# betaV2_3.net
KiCad netlist of a schematic drawn in Altium Designer
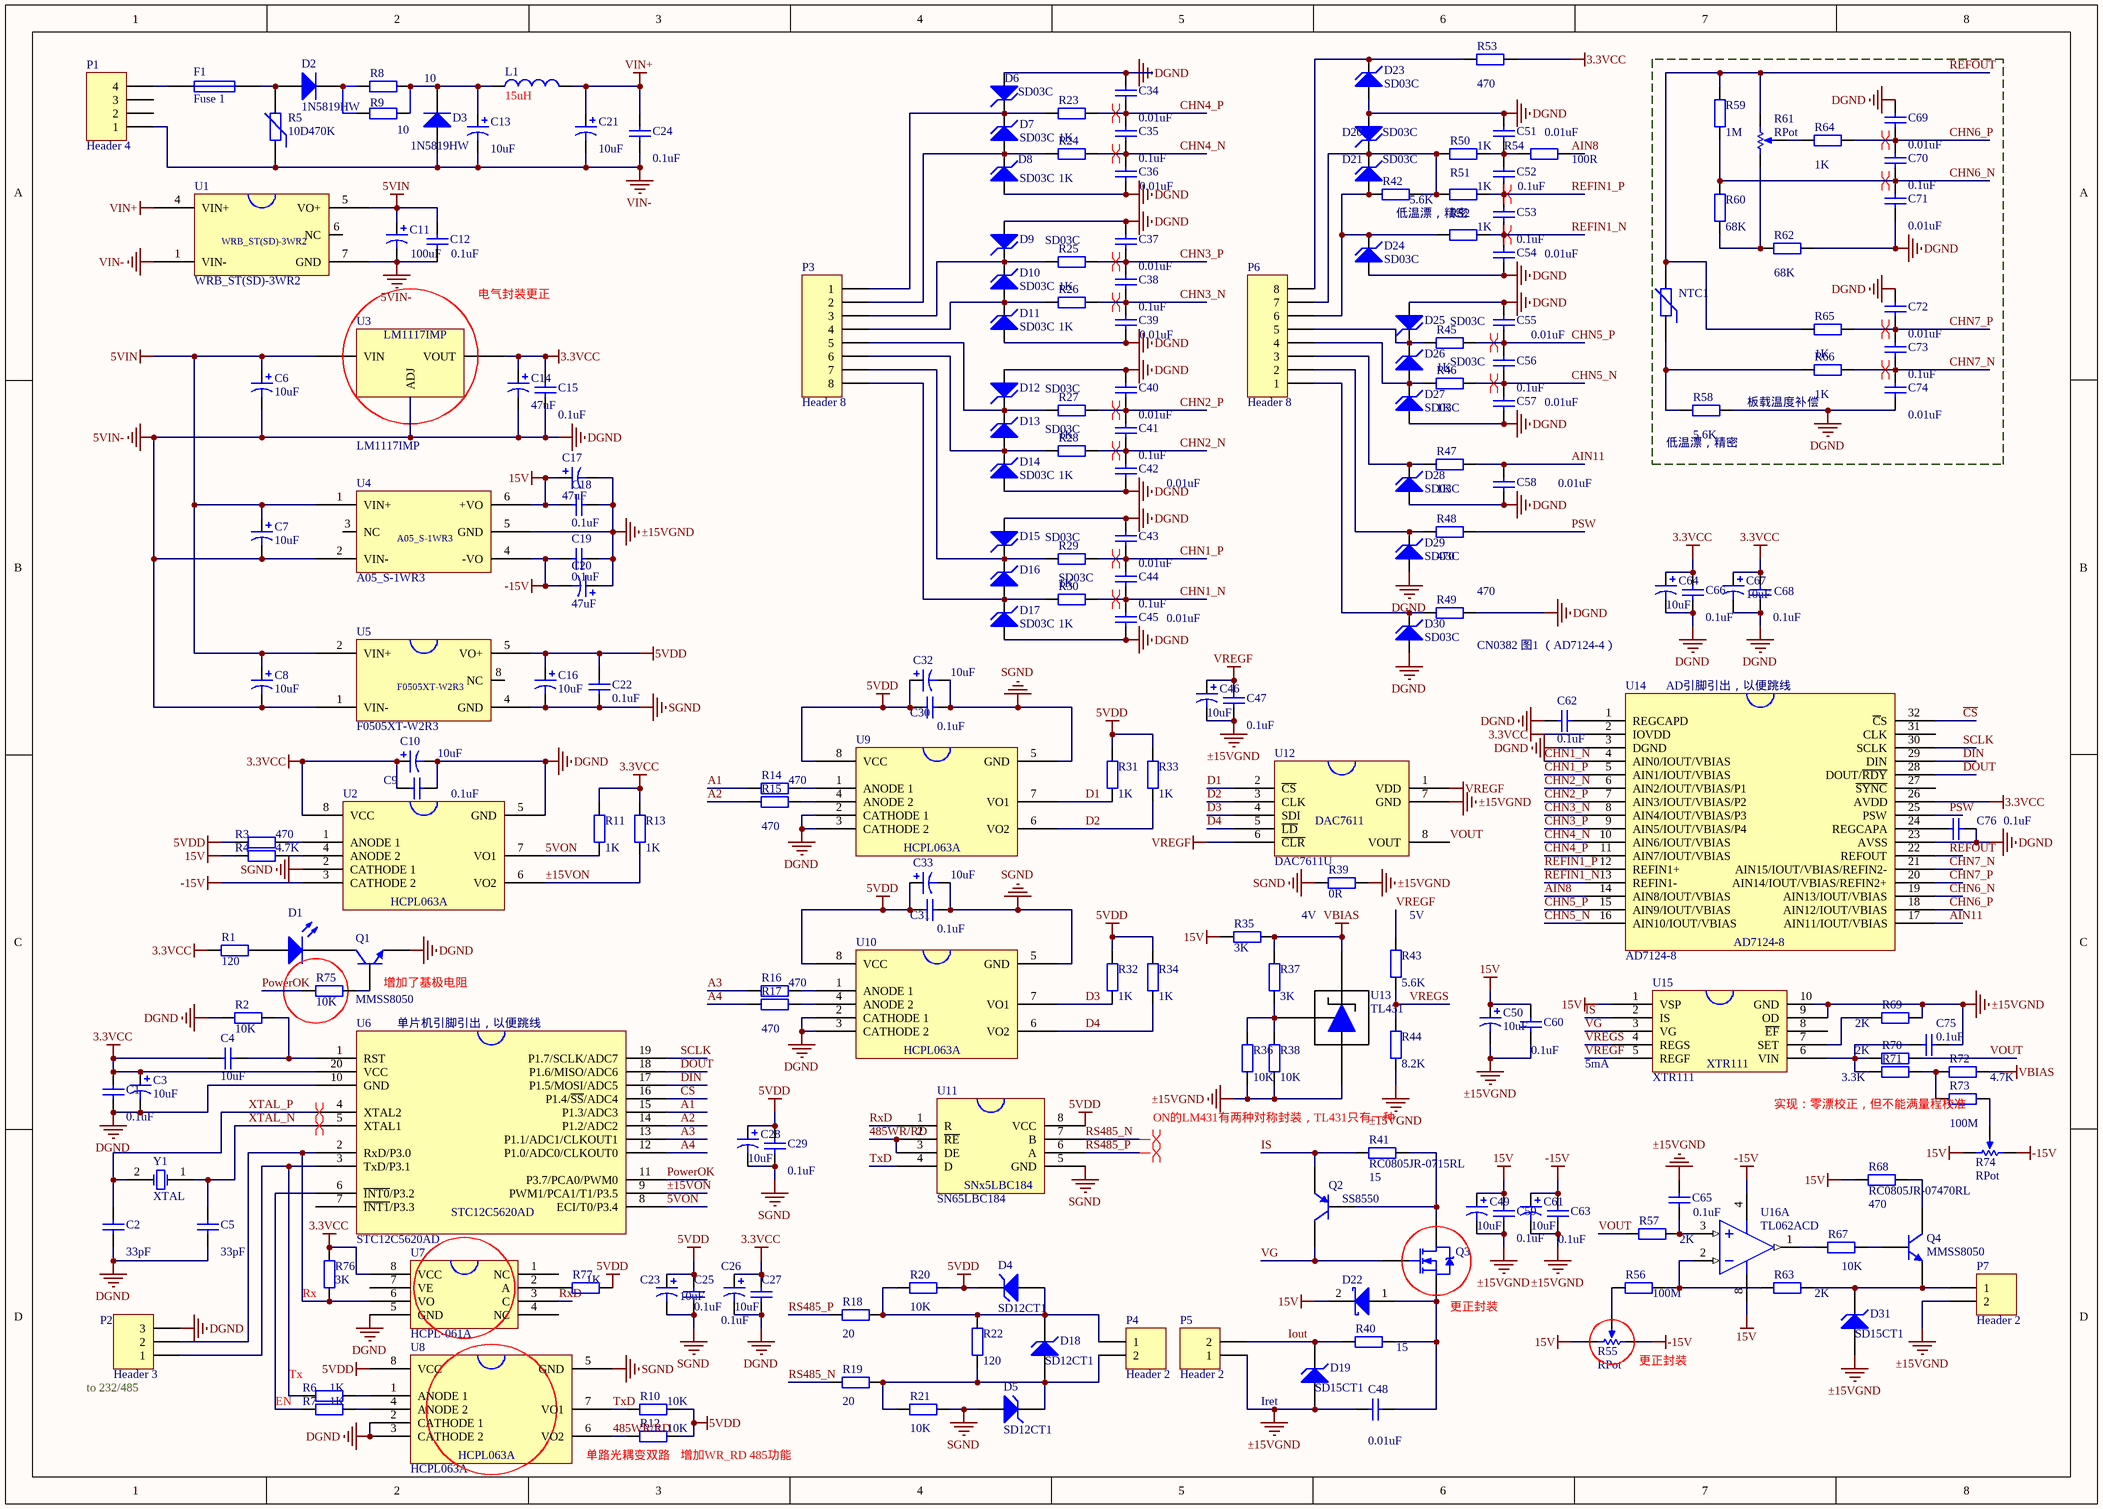
[diagram p0: betaV2.3.SchDoc]

(export (version "E")
  (design (tool "Eeschema 10.0.6"))
  (components
    (comp (ref "C1")
      (value "0.1uF")
      (footprint "0805c")
      (description "Capacitor")
      (fields (field (name "Comment") "CC0805MRX7R9BB104"))
      (libsource (lib "Miscellaneous Devices") (part "Cap"))
    )
    (comp (ref "C2")
      (value "33pF")
      (footprint "0805c")
      (description "Capacitor")
      (fields (field (name "Comment") "CC0805MRX7R9BB330") (field (name "PUBLISHER") "Altium Limited"))
      (libsource (lib "Miscellaneous Devices") (part "Cap"))
    )
    (comp (ref "C3")
      (value "10uF")
      (footprint "CB")
      (description "Polarized Capacitor (Radial)")
      (fields (field (name "Comment") "T494B106M006AHAUTO") (field (name "PUBLISHER") "Altium Limited"))
      (libsource (lib "Miscellaneous Devices") (part "Cap Pol1"))
    )
    (comp (ref "C4")
      (value "10uF")
      (footprint "0805c")
      (description "Capacitor")
      (fields (field (name "Comment") "CC0805MRX7R9BB106"))
      (libsource (lib "Miscellaneous Devices") (part "Cap"))
    )
    (comp (ref "C5")
      (value "33pF")
      (footprint "0805c")
      (description "Capacitor")
      (fields (field (name "Comment") "CC0805MRX7R9BB330") (field (name "PUBLISHER") "Altium Limited"))
      (libsource (lib "Miscellaneous Devices") (part "Cap"))
    )
    (comp (ref "C6")
      (value "10uF")
      (footprint "CB")
      (description "Polarized Capacitor (Radial)")
      (fields (field (name "Comment") "T494B106M006AHAUTO") (field (name "PUBLISHER") "Altium Limited"))
      (libsource (lib "Miscellaneous Devices") (part "Cap Pol1"))
    )
    (comp (ref "C7")
      (value "10uF")
      (footprint "CB")
      (description "Polarized Capacitor (Radial)")
      (fields (field (name "Comment") "T494B106M006AHAUTO") (field (name "PUBLISHER") "Altium Limited"))
      (libsource (lib "Miscellaneous Devices") (part "Cap Pol1"))
    )
    (comp (ref "C8")
      (value "10uF")
      (footprint "CB")
      (description "Polarized Capacitor (Radial)")
      (fields (field (name "Comment") "T494B106M006AHAUTO") (field (name "PUBLISHER") "Altium Limited"))
      (libsource (lib "Miscellaneous Devices") (part "Cap Pol1"))
    )
    (comp (ref "C9")
      (value "0.1uF")
      (footprint "0805c")
      (description "Capacitor")
      (fields (field (name "Comment") "CC0805MRX7R9BB104") (field (name "PUBLISHER") "Altium Limited"))
      (libsource (lib "Miscellaneous Devices") (part "Cap"))
    )
    (comp (ref "C10")
      (value "10uF")
      (footprint "CB")
      (description "Polarized Capacitor (Radial)")
      (fields (field (name "Comment") "T494B106M006AHAUTO") (field (name "PUBLISHER") "Altium Limited"))
      (libsource (lib "Miscellaneous Devices") (part "Cap Pol1"))
    )
    (comp (ref "C11")
      (value "100uF")
      (footprint "CB")
      (description "Polarized Capacitor (Radial)")
      (fields (field (name "Comment") "T494B107M006AHAUTO") (field (name "PUBLISHER") "Altium Limited"))
      (libsource (lib "Miscellaneous Devices") (part "Cap Pol1"))
    )
    (comp (ref "C12")
      (value "0.1uF")
      (footprint "0805c")
      (description "Capacitor")
      (fields (field (name "Comment") "CC0805MRX7R9BB104") (field (name "PUBLISHER") "Altium Limited"))
      (libsource (lib "Miscellaneous Devices") (part "Cap"))
    )
    (comp (ref "C13")
      (value "10uF")
      (footprint "Φ6.3×11.5")
      (description "Polarized Capacitor (Radial)")
      (fields (field (name "Comment") "ECR1HQG100M-063007") (field (name "PUBLISHER") "Altium Limited"))
      (libsource (lib "Miscellaneous Devices") (part "Cap Pol1"))
    )
    (comp (ref "C14")
      (value "47uF")
      (footprint "CB")
      (description "Polarized Capacitor (Radial)")
      (fields (field (name "Comment") "T494B476M010AHAUTO") (field (name "PUBLISHER") "Altium Limited"))
      (libsource (lib "Miscellaneous Devices") (part "Cap Pol1"))
    )
    (comp (ref "C15")
      (value "0.1uF")
      (footprint "0805c")
      (description "Capacitor")
      (fields (field (name "Comment") "CC0805MRX7R9BB104") (field (name "PUBLISHER") "Altium Limited"))
      (libsource (lib "Miscellaneous Devices") (part "Cap"))
    )
    (comp (ref "C16")
      (value "10uF")
      (footprint "CB")
      (description "Polarized Capacitor (Radial)")
      (fields (field (name "Comment") "T494B106M006AHAUTO") (field (name "PUBLISHER") "Altium Limited"))
      (libsource (lib "Miscellaneous Devices") (part "Cap Pol1"))
    )
    (comp (ref "C17")
      (value "47uF")
      (footprint "CB")
      (description "Polarized Capacitor (Radial)")
      (fields (field (name "Comment") "T494B476K025ATAUTO") (field (name "PUBLISHER") "Altium Limited"))
      (libsource (lib "Miscellaneous Devices") (part "Cap Pol1"))
    )
    (comp (ref "C18")
      (value "0.1uF")
      (footprint "0805c")
      (description "Capacitor")
      (fields (field (name "Comment") "CC0805MRX7R9BB104") (field (name "PUBLISHER") "Altium Limited"))
      (libsource (lib "Miscellaneous Devices") (part "Cap"))
    )
    (comp (ref "C19")
      (value "0.1uF")
      (footprint "0805c")
      (description "Capacitor")
      (fields (field (name "Comment") "CC0805MRX7R9BB104") (field (name "PUBLISHER") "Altium Limited"))
      (libsource (lib "Miscellaneous Devices") (part "Cap"))
    )
    (comp (ref "C20")
      (value "47uF")
      (footprint "CB")
      (description "Polarized Capacitor (Radial)")
      (fields (field (name "Comment") "T494B476K025ATAUTO") (field (name "PUBLISHER") "Altium Limited"))
      (libsource (lib "Miscellaneous Devices") (part "Cap Pol1"))
    )
    (comp (ref "C21")
      (value "10uF")
      (footprint "Φ6.3×11.5")
      (description "Polarized Capacitor (Radial)")
      (fields (field (name "Comment") "ECR1HQG100M-063007") (field (name "PUBLISHER") "Altium Limited"))
      (libsource (lib "Miscellaneous Devices") (part "Cap Pol1"))
    )
    (comp (ref "C22")
      (value "0.1uF")
      (footprint "0805c")
      (description "Capacitor")
      (fields (field (name "Comment") "CC0805MRX7R9BB104") (field (name "PUBLISHER") "Altium Limited"))
      (libsource (lib "Miscellaneous Devices") (part "Cap"))
    )
    (comp (ref "C23")
      (value "10uF")
      (footprint "CB")
      (description "Polarized Capacitor (Radial)")
      (fields (field (name "Comment") "T494B106M006AHAUTO") (field (name "PUBLISHER") "Altium Limited"))
      (libsource (lib "Miscellaneous Devices") (part "Cap Pol1"))
    )
    (comp (ref "C24")
      (value "0.1uF")
      (footprint "0805c")
      (description "Capacitor")
      (fields (field (name "Comment") "CC0805MRX7R9BB104") (field (name "PUBLISHER") "Altium Limited"))
      (libsource (lib "Miscellaneous Devices") (part "Cap"))
    )
    (comp (ref "C25")
      (value "0.1uF")
      (footprint "0805c")
      (description "Capacitor")
      (fields (field (name "Comment") "CC0805MRX7R9BB104") (field (name "PUBLISHER") "Altium Limited"))
      (libsource (lib "Miscellaneous Devices") (part "Cap"))
    )
    (comp (ref "C26")
      (value "10uF")
      (footprint "CB")
      (description "Polarized Capacitor (Radial)")
      (fields (field (name "Comment") "T494B106M006AHAUTO") (field (name "PUBLISHER") "Altium Limited"))
      (libsource (lib "Miscellaneous Devices") (part "Cap Pol1"))
    )
    (comp (ref "C27")
      (value "0.1uF")
      (footprint "0805c")
      (description "Capacitor")
      (fields (field (name "Comment") "CC0805MRX7R9BB104") (field (name "PUBLISHER") "Altium Limited"))
      (libsource (lib "Miscellaneous Devices") (part "Cap"))
    )
    (comp (ref "C28")
      (value "10uF")
      (footprint "CB")
      (description "Polarized Capacitor (Radial)")
      (fields (field (name "Comment") "T494B106M006AHAUTO") (field (name "PUBLISHER") "Altium Limited"))
      (libsource (lib "Miscellaneous Devices") (part "Cap Pol1"))
    )
    (comp (ref "C29")
      (value "0.1uF")
      (footprint "0805c")
      (description "Capacitor")
      (fields (field (name "Comment") "CC0805MRX7R9BB104") (field (name "PUBLISHER") "Altium Limited"))
      (libsource (lib "Miscellaneous Devices") (part "Cap"))
    )
    (comp (ref "C30")
      (value "0.1uF")
      (footprint "0805c")
      (description "Capacitor")
      (fields (field (name "Comment") "CC0805MRX7R9BB104") (field (name "PUBLISHER") "Altium Limited"))
      (libsource (lib "Miscellaneous Devices") (part "Cap"))
    )
    (comp (ref "C31")
      (value "0.1uF")
      (footprint "0805c")
      (description "Capacitor")
      (fields (field (name "Comment") "CC0805MRX7R9BB104") (field (name "PUBLISHER") "Altium Limited"))
      (libsource (lib "Miscellaneous Devices") (part "Cap"))
    )
    (comp (ref "C32")
      (value "10uF")
      (footprint "CB")
      (description "Polarized Capacitor (Radial)")
      (fields (field (name "Comment") "T494B106M006AHAUTO") (field (name "PUBLISHER") "Altium Limited"))
      (libsource (lib "Miscellaneous Devices") (part "Cap Pol1"))
    )
    (comp (ref "C33")
      (value "10uF")
      (footprint "CB")
      (description "Polarized Capacitor (Radial)")
      (fields (field (name "Comment") "T494B106M006AHAUTO") (field (name "PUBLISHER") "Altium Limited"))
      (libsource (lib "Miscellaneous Devices") (part "Cap Pol1"))
    )
    (comp (ref "C34")
      (value "0.01uF")
      (footprint "0805c")
      (description "Capacitor")
      (fields (field (name "Comment") "CC0805MRX7R9BB103") (field (name "PUBLISHER") "Altium Limited"))
      (libsource (lib "Miscellaneous Devices") (part "Cap"))
    )
    (comp (ref "C35")
      (value "0.1uF")
      (footprint "0805c")
      (description "Capacitor")
      (fields (field (name "Comment") "CC0805MRX7R9BB104") (field (name "PUBLISHER") "Altium Limited"))
      (libsource (lib "Miscellaneous Devices") (part "Cap"))
    )
    (comp (ref "C36")
      (value "0.01uF")
      (footprint "0805c")
      (description "Capacitor")
      (fields (field (name "Comment") "CC0805MRX7R9BB103") (field (name "PUBLISHER") "Altium Limited"))
      (libsource (lib "Miscellaneous Devices") (part "Cap"))
    )
    (comp (ref "C37")
      (value "0.01uF")
      (footprint "0805c")
      (description "Capacitor")
      (fields (field (name "Comment") "CC0805MRX7R9BB103") (field (name "PUBLISHER") "Altium Limited"))
      (libsource (lib "Miscellaneous Devices") (part "Cap"))
    )
    (comp (ref "C38")
      (value "0.1uF")
      (footprint "0805c")
      (description "Capacitor")
      (fields (field (name "Comment") "CC0805MRX7R9BB104") (field (name "PUBLISHER") "Altium Limited"))
      (libsource (lib "Miscellaneous Devices") (part "Cap"))
    )
    (comp (ref "C39")
      (value "0.01uF")
      (footprint "0805c")
      (description "Capacitor")
      (fields (field (name "Comment") "CC0805MRX7R9BB103") (field (name "PUBLISHER") "Altium Limited"))
      (libsource (lib "Miscellaneous Devices") (part "Cap"))
    )
    (comp (ref "C40")
      (value "0.01uF")
      (footprint "0805c")
      (description "Capacitor")
      (fields (field (name "Comment") "CC0805MRX7R9BB103") (field (name "PUBLISHER") "Altium Limited"))
      (libsource (lib "Miscellaneous Devices") (part "Cap"))
    )
    (comp (ref "C41")
      (value "0.1uF")
      (footprint "0805c")
      (description "Capacitor")
      (fields (field (name "Comment") "CC0805MRX7R9BB104") (field (name "PUBLISHER") "Altium Limited"))
      (libsource (lib "Miscellaneous Devices") (part "Cap"))
    )
    (comp (ref "C42")
      (value "0.01uF")
      (footprint "0805c")
      (description "Capacitor")
      (fields (field (name "Comment") "CC0805MRX7R9BB103") (field (name "PUBLISHER") "Altium Limited"))
      (libsource (lib "Miscellaneous Devices") (part "Cap"))
    )
    (comp (ref "C43")
      (value "0.01uF")
      (footprint "0805c")
      (description "Capacitor")
      (fields (field (name "Comment") "CC0805MRX7R9BB103") (field (name "PUBLISHER") "Altium Limited"))
      (libsource (lib "Miscellaneous Devices") (part "Cap"))
    )
    (comp (ref "C44")
      (value "0.1uF")
      (footprint "0805c")
      (description "Capacitor")
      (fields (field (name "Comment") "CC0805MRX7R9BB104") (field (name "PUBLISHER") "Altium Limited"))
      (libsource (lib "Miscellaneous Devices") (part "Cap"))
    )
    (comp (ref "C45")
      (value "0.01uF")
      (footprint "0805c")
      (description "Capacitor")
      (fields (field (name "Comment") "CC0805MRX7R9BB103") (field (name "PUBLISHER") "Altium Limited"))
      (libsource (lib "Miscellaneous Devices") (part "Cap"))
    )
    (comp (ref "C46")
      (value "10uF")
      (footprint "CB")
      (description "Polarized Capacitor (Radial)")
      (fields (field (name "Comment") "T494B106M006AHAUTO") (field (name "PUBLISHER") "Altium Limited"))
      (libsource (lib "Miscellaneous Devices") (part "Cap Pol1"))
    )
    (comp (ref "C47")
      (value "0.1uF")
      (footprint "0805c")
      (description "Capacitor")
      (fields (field (name "Comment") "CC0805MRX7R9BB104") (field (name "PUBLISHER") "Altium Limited"))
      (libsource (lib "Miscellaneous Devices") (part "Cap"))
    )
    (comp (ref "C48")
      (value "0.01uF")
      (footprint "0805c")
      (description "Capacitor")
      (fields (field (name "Comment") "CC0805MRX7R9BB103") (field (name "PUBLISHER") "Altium Limited"))
      (libsource (lib "Miscellaneous Devices") (part "Cap"))
    )
    (comp (ref "C49")
      (value "10uF")
      (footprint "CB")
      (description "Polarized Capacitor (Radial)")
      (fields (field (name "Comment") "T494B106M025AHAUTO") (field (name "PUBLISHER") "Altium Limited"))
      (libsource (lib "Miscellaneous Devices") (part "Cap Pol1"))
    )
    (comp (ref "C50")
      (value "10uF")
      (footprint "CB")
      (description "Polarized Capacitor (Radial)")
      (fields (field (name "Comment") "T494B106M025AHAUTO") (field (name "PUBLISHER") "Altium Limited"))
      (libsource (lib "Miscellaneous Devices") (part "Cap Pol1"))
    )
    (comp (ref "C51")
      (value "0.01uF")
      (footprint "0805c")
      (description "Capacitor")
      (fields (field (name "Comment") "CC0805MRX7R9BB103") (field (name "PUBLISHER") "Altium Limited"))
      (libsource (lib "Miscellaneous Devices") (part "Cap"))
    )
    (comp (ref "C52")
      (value "0.1uF")
      (footprint "0805c")
      (description "Capacitor")
      (fields (field (name "Comment") "CC0805MRX7R9BB104") (field (name "PUBLISHER") "Altium Limited"))
      (libsource (lib "Miscellaneous Devices") (part "Cap"))
    )
    (comp (ref "C53")
      (value "0.1uF")
      (footprint "0805c")
      (description "Capacitor")
      (fields (field (name "Comment") "CC0805MRX7R9BB104") (field (name "PUBLISHER") "Altium Limited"))
      (libsource (lib "Miscellaneous Devices") (part "Cap"))
    )
    (comp (ref "C54")
      (value "0.01uF")
      (footprint "0805c")
      (description "Capacitor")
      (fields (field (name "Comment") "CC0805MRX7R9BB103") (field (name "PUBLISHER") "Altium Limited"))
      (libsource (lib "Miscellaneous Devices") (part "Cap"))
    )
    (comp (ref "C55")
      (value "0.01uF")
      (footprint "0805c")
      (description "Capacitor")
      (fields (field (name "Comment") "CC0805MRX7R9BB103") (field (name "PUBLISHER") "Altium Limited"))
      (libsource (lib "Miscellaneous Devices") (part "Cap"))
    )
    (comp (ref "C56")
      (value "0.1uF")
      (footprint "0805c")
      (description "Capacitor")
      (fields (field (name "Comment") "CC0805MRX7R9BB104") (field (name "PUBLISHER") "Altium Limited"))
      (libsource (lib "Miscellaneous Devices") (part "Cap"))
    )
    (comp (ref "C57")
      (value "0.01uF")
      (footprint "0805c")
      (description "Capacitor")
      (fields (field (name "Comment") "CC0805MRX7R9BB103") (field (name "PUBLISHER") "Altium Limited"))
      (libsource (lib "Miscellaneous Devices") (part "Cap"))
    )
    (comp (ref "C58")
      (value "0.01uF")
      (footprint "0805c")
      (description "Capacitor")
      (fields (field (name "Comment") "CC0805MRX7R9BB103") (field (name "PUBLISHER") "Altium Limited"))
      (libsource (lib "Miscellaneous Devices") (part "Cap"))
    )
    (comp (ref "C59")
      (value "0.1uF")
      (footprint "0805c")
      (description "Capacitor")
      (fields (field (name "Comment") "CC0805MRX7R9BB104") (field (name "PUBLISHER") "Altium Limited"))
      (libsource (lib "Miscellaneous Devices") (part "Cap"))
    )
    (comp (ref "C60")
      (value "0.1uF")
      (footprint "0805c")
      (description "Capacitor")
      (fields (field (name "Comment") "CC0805MRX7R9BB104") (field (name "PUBLISHER") "Altium Limited"))
      (libsource (lib "Miscellaneous Devices") (part "Cap"))
    )
    (comp (ref "C61")
      (value "10uF")
      (footprint "CB")
      (description "Polarized Capacitor (Radial)")
      (fields (field (name "Comment") "T494B106M025AHAUTO") (field (name "PUBLISHER") "Altium Limited"))
      (libsource (lib "Miscellaneous Devices") (part "Cap Pol1"))
    )
    (comp (ref "C62")
      (value "0.1uF")
      (footprint "0805c")
      (description "Capacitor")
      (fields (field (name "Comment") "CC0805MRX7R9BB104") (field (name "PUBLISHER") "Altium Limited"))
      (libsource (lib "Miscellaneous Devices") (part "Cap"))
    )
    (comp (ref "C63")
      (value "0.1uF")
      (footprint "0805c")
      (description "Capacitor")
      (fields (field (name "Comment") "CC0805MRX7R9BB104") (field (name "PUBLISHER") "Altium Limited"))
      (libsource (lib "Miscellaneous Devices") (part "Cap"))
    )
    (comp (ref "C64")
      (value "10uF")
      (footprint "CB")
      (description "Polarized Capacitor (Radial)")
      (fields (field (name "Comment") "T494B106M006AHAUTO") (field (name "PUBLISHER") "Altium Limited"))
      (libsource (lib "Miscellaneous Devices") (part "Cap Pol1"))
    )
    (comp (ref "C65")
      (value "0.1uF")
      (footprint "0805c")
      (description "Capacitor")
      (fields (field (name "Comment") "CC0805MRX7R9BB104") (field (name "PUBLISHER") "Altium Limited"))
      (libsource (lib "Miscellaneous Devices") (part "Cap"))
    )
    (comp (ref "C66")
      (value "0.1uF")
      (footprint "0805c")
      (description "Capacitor")
      (fields (field (name "Comment") "CC0805MRX7R9BB104") (field (name "PUBLISHER") "Altium Limited"))
      (libsource (lib "Miscellaneous Devices") (part "Cap"))
    )
    (comp (ref "C67")
      (value "10uF")
      (footprint "CB")
      (description "Polarized Capacitor (Radial)")
      (fields (field (name "Comment") "T494B106M006AHAUTO") (field (name "PUBLISHER") "Altium Limited"))
      (libsource (lib "Miscellaneous Devices") (part "Cap Pol1"))
    )
    (comp (ref "C68")
      (value "0.1uF")
      (footprint "0805c")
      (description "Capacitor")
      (fields (field (name "Comment") "CC0805MRX7R9BB104") (field (name "PUBLISHER") "Altium Limited"))
      (libsource (lib "Miscellaneous Devices") (part "Cap"))
    )
    (comp (ref "C69")
      (value "0.01uF")
      (footprint "0805c")
      (description "Capacitor")
      (fields (field (name "Comment") "CC0805MRX7R9BB103") (field (name "PUBLISHER") "Altium Limited"))
      (libsource (lib "Miscellaneous Devices") (part "Cap"))
    )
    (comp (ref "C70")
      (value "0.1uF")
      (footprint "0805c")
      (description "Capacitor")
      (fields (field (name "Comment") "CC0805MRX7R9BB104") (field (name "PUBLISHER") "Altium Limited"))
      (libsource (lib "Miscellaneous Devices") (part "Cap"))
    )
    (comp (ref "C71")
      (value "0.01uF")
      (footprint "0805c")
      (description "Capacitor")
      (fields (field (name "Comment") "CC0805MRX7R9BB103") (field (name "PUBLISHER") "Altium Limited"))
      (libsource (lib "Miscellaneous Devices") (part "Cap"))
    )
    (comp (ref "C72")
      (value "0.01uF")
      (footprint "0805c")
      (description "Capacitor")
      (fields (field (name "Comment") "CC0805MRX7R9BB103") (field (name "PUBLISHER") "Altium Limited"))
      (libsource (lib "Miscellaneous Devices") (part "Cap"))
    )
    (comp (ref "C73")
      (value "0.1uF")
      (footprint "0805c")
      (description "Capacitor")
      (fields (field (name "Comment") "CC0805MRX7R9BB104") (field (name "PUBLISHER") "Altium Limited"))
      (libsource (lib "Miscellaneous Devices") (part "Cap"))
    )
    (comp (ref "C74")
      (value "0.01uF")
      (footprint "0805c")
      (description "Capacitor")
      (fields (field (name "Comment") "CC0805MRX7R9BB103") (field (name "PUBLISHER") "Altium Limited"))
      (libsource (lib "Miscellaneous Devices") (part "Cap"))
    )
    (comp (ref "C75")
      (value "0.1uF")
      (footprint "0805c")
      (description "Capacitor")
      (fields (field (name "Comment") "CC0805MRX7R9BB104") (field (name "PUBLISHER") "Altium Limited"))
      (libsource (lib "Miscellaneous Devices") (part "Cap"))
    )
    (comp (ref "C76")
      (value "0.1uF")
      (footprint "0805c")
      (description "Capacitor")
      (fields (field (name "Comment") "CC0805MRX7R9BB104") (field (name "PUBLISHER") "Altium Limited"))
      (libsource (lib "Miscellaneous Devices") (part "Cap"))
    )
    (comp (ref "D1")
      (value "150080GS75000")
      (footprint "LEDΦ3.0")
      (description "Typical RED, GREEN, YELLOW, AMBER GaAs LED")
      (fields (field (name "PUBLISHER") "Altium Limited"))
      (libsource (lib "Miscellaneous Devices") (part "LED2"))
    )
    (comp (ref "D2")
      (value "1N5819HW")
      (footprint "sod123")
      (description "Default Diode")
      (fields (field (name "PUBLISHER") "Altium Limited"))
      (libsource (lib "Miscellaneous Devices") (part "Diode"))
    )
    (comp (ref "D3")
      (value "1N5819HW")
      (footprint "sod123")
      (description "Default Diode")
      (fields (field (name "PUBLISHER") "Altium Limited"))
      (libsource (lib "Miscellaneous Devices") (part "Diode"))
    )
    (comp (ref "D4")
      (value "SD12CT1")
      (footprint "sod323")
      (description "Zener Diode")
      (fields (field (name "PUBLISHER") "Altium Limited"))
      (libsource (lib "Miscellaneous Devices") (part "D Zener"))
    )
    (comp (ref "D5")
      (value "SD12CT1")
      (footprint "sod323")
      (description "Zener Diode")
      (fields (field (name "PUBLISHER") "Altium Limited"))
      (libsource (lib "Miscellaneous Devices") (part "D Zener"))
    )
    (comp (ref "D6")
      (value "SD03C")
      (footprint "sod323")
      (libsource (lib "Standard-V0.0") (part "TVS DIODE"))
    )
    (comp (ref "D7")
      (value "SD03C")
      (footprint "sod323")
      (libsource (lib "Standard-V0.0") (part "TVS DIODE"))
    )
    (comp (ref "D8")
      (value "SD03C")
      (footprint "sod323")
      (libsource (lib "Standard-V0.0") (part "TVS DIODE"))
    )
    (comp (ref "D9")
      (value "SD03C")
      (footprint "sod323")
      (libsource (lib "Standard-V0.0") (part "TVS DIODE"))
    )
    (comp (ref "D10")
      (value "SD03C")
      (footprint "sod323")
      (libsource (lib "Standard-V0.0") (part "TVS DIODE"))
    )
    (comp (ref "D11")
      (value "SD03C")
      (footprint "sod323")
      (libsource (lib "Standard-V0.0") (part "TVS DIODE"))
    )
    (comp (ref "D12")
      (value "SD03C")
      (footprint "sod323")
      (libsource (lib "Standard-V0.0") (part "TVS DIODE"))
    )
    (comp (ref "D13")
      (value "SD03C")
      (footprint "sod323")
      (libsource (lib "Standard-V0.0") (part "TVS DIODE"))
    )
    (comp (ref "D14")
      (value "SD03C")
      (footprint "sod323")
      (libsource (lib "Standard-V0.0") (part "TVS DIODE"))
    )
    (comp (ref "D15")
      (value "SD03C")
      (footprint "sod323")
      (libsource (lib "Standard-V0.0") (part "TVS DIODE"))
    )
    (comp (ref "D16")
      (value "SD03C")
      (footprint "sod323")
      (libsource (lib "Standard-V0.0") (part "TVS DIODE"))
    )
    (comp (ref "D17")
      (value "SD03C")
      (footprint "sod323")
      (libsource (lib "Standard-V0.0") (part "TVS DIODE"))
    )
    (comp (ref "D18")
      (value "SD12CT1")
      (footprint "sod323")
      (description "Zener Diode")
      (fields (field (name "PUBLISHER") "Altium Limited"))
      (libsource (lib "Miscellaneous Devices") (part "D Zener"))
    )
    (comp (ref "D19")
      (value "SD15CT1")
      (footprint "sod323")
      (description "Zener Diode")
      (fields (field (name "PUBLISHER") "Altium Limited"))
      (libsource (lib "Miscellaneous Devices") (part "D Zener"))
    )
    (comp (ref "D20")
      (value "SD03C")
      (footprint "sod323")
      (libsource (lib "Standard-V0.0") (part "TVS DIODE"))
    )
    (comp (ref "D21")
      (value "SD03C")
      (footprint "sod323")
      (libsource (lib "Standard-V0.0") (part "TVS DIODE"))
    )
    (comp (ref "D22")
      (value "RB160MM-50TF")
      (footprint "sod123")
      (description "Schottky Diode")
      (fields (field (name "PUBLISHER") "Altium Limited"))
      (libsource (lib "Miscellaneous Devices") (part "D Schottky"))
    )
    (comp (ref "D23")
      (value "SD03C")
      (footprint "sod323")
      (libsource (lib "Standard-V0.0") (part "TVS DIODE"))
    )
    (comp (ref "D24")
      (value "SD03C")
      (footprint "sod323")
      (libsource (lib "Standard-V0.0") (part "TVS DIODE"))
    )
    (comp (ref "D25")
      (value "SD03C")
      (footprint "sod323")
      (libsource (lib "Standard-V0.0") (part "TVS DIODE"))
    )
    (comp (ref "D26")
      (value "SD03C")
      (footprint "sod323")
      (libsource (lib "Standard-V0.0") (part "TVS DIODE"))
    )
    (comp (ref "D27")
      (value "SD03C")
      (footprint "sod323")
      (libsource (lib "Standard-V0.0") (part "TVS DIODE"))
    )
    (comp (ref "D28")
      (value "SD03C")
      (footprint "sod323")
      (libsource (lib "Standard-V0.0") (part "TVS DIODE"))
    )
    (comp (ref "D29")
      (value "SD03C")
      (footprint "sod323")
      (libsource (lib "Standard-V0.0") (part "TVS DIODE"))
    )
    (comp (ref "D30")
      (value "SD03C")
      (footprint "sod323")
      (libsource (lib "Standard-V0.0") (part "TVS DIODE"))
    )
    (comp (ref "D31")
      (value "SD15CT1")
      (footprint "sod323")
      (description "Zener Diode")
      (fields (field (name "PUBLISHER") "Altium Limited"))
      (libsource (lib "Miscellaneous Devices") (part "D Zener"))
    )
    (comp (ref "F1")
      (value "Fuse 1")
      (footprint "0805r")
      (description "Fuse")
      (fields (field (name "PUBLISHER") "Altium Limited"))
      (libsource (lib "Miscellaneous Devices") (part "Fuse 1"))
    )
    (comp (ref "L1")
      (value "15uH")
      (footprint "vls4012")
      (fields (field (name "Comment") "VLS4012HBX-150M"))
      (libsource (lib "Miscellaneous Devices") (part "Inductor"))
    )
    (comp (ref "NTC1")
      (value "NTCS0805E3103JHT")
      (footprint "0805r")
      (description "Varistor (Voltage-Sensitive Resistor)")
      (fields (field (name "PUBLISHER") "Altium Limited"))
      (libsource (lib "Miscellaneous Devices") (part "Res Varistor"))
    )
    (comp (ref "P1")
      (value "Header 4")
      (footprint "HDR1X4")
      (description "Header, 4-Pin")
      (fields (field (name "PUBLISHER") "Altium Limited"))
      (libsource (lib "Miscellaneous Connectors") (part "Header 4"))
    )
    (comp (ref "P2")
      (value "Header 3")
      (footprint "HDR1X3")
      (description "Header, 3-Pin")
      (fields (field (name "PUBLISHER") "Altium Limited"))
      (libsource (lib "Miscellaneous Connectors") (part "Header 3"))
    )
    (comp (ref "P3")
      (value "Header 8")
      (footprint "HDR1X8")
      (description "Header, 8-Pin")
      (fields (field (name "PUBLISHER") "Altium Limited"))
      (libsource (lib "Miscellaneous Connectors") (part "Header 8"))
    )
    (comp (ref "P4")
      (value "Header 2")
      (footprint "HDR1X2")
      (description "Header, 2-Pin")
      (fields (field (name "PUBLISHER") "Altium Limited"))
      (libsource (lib "") (part "Header 2_1"))
    )
    (comp (ref "P5")
      (value "Header 2")
      (footprint "HDR1X2")
      (description "Header, 2-Pin")
      (fields (field (name "PUBLISHER") "Altium Limited"))
      (libsource (lib "Miscellaneous Connectors") (part "Header 2"))
    )
    (comp (ref "P6")
      (value "Header 8")
      (footprint "HDR1X8")
      (description "Header, 8-Pin")
      (fields (field (name "PUBLISHER") "Altium Limited"))
      (libsource (lib "") (part "Header 8_1"))
    )
    (comp (ref "P7")
      (value "Header 2")
      (footprint "HDR1X2")
      (description "Header, 2-Pin")
      (fields (field (name "PUBLISHER") "Altium Limited"))
      (libsource (lib "") (part "Header 2_1"))
    )
    (comp (ref "Q1")
      (value "MMSS8050")
      (footprint "SOT-23-BJT")
      (description "NPN Bipolar Transistor")
      (fields (field (name "PUBLISHER") "Altium Limited"))
      (libsource (lib "Miscellaneous Devices") (part "NPN"))
    )
    (comp (ref "Q2")
      (value "SS8550")
      (footprint "SOT-23-BJT")
      (description "PNP Bipolar Transistor")
      (fields (field (name "PUBLISHER") "Altium Limited"))
      (libsource (lib "Miscellaneous Devices") (part "PNP"))
    )
    (comp (ref "Q3")
      (value "SI2309")
      (footprint "SOT-23-MOS")
      (description "N-Channel Power MOSFET")
      (fields (field (name "PUBLISHER") "Altium Limited"))
      (libsource (lib "Miscellaneous Devices") (part "NMOS-2"))
    )
    (comp (ref "Q4")
      (value "MMSS8050")
      (footprint "SOT-23-BJT")
      (description "NPN Bipolar Transistor")
      (fields (field (name "PUBLISHER") "Altium Limited"))
      (libsource (lib "Miscellaneous Devices") (part "NPN"))
    )
    (comp (ref "R1")
      (value "120")
      (footprint "0805R")
      (description "Resistor")
      (fields (field (name "Comment") "RC0805JR-07120RL") (field (name "PUBLISHER") "Altium Limited"))
      (libsource (lib "") (part "Res2_3"))
    )
    (comp (ref "R2")
      (value "10K")
      (footprint "0805R")
      (description "Resistor")
      (fields (field (name "Comment") "RC0805JR-0710KL") (field (name "PUBLISHER") "Altium Limited"))
      (libsource (lib "") (part "Res2_3"))
    )
    (comp (ref "R3")
      (value "470")
      (footprint "0805R")
      (description "Resistor")
      (fields (field (name "Comment") "RC0805JR-07470RL") (field (name "PUBLISHER") "Altium Limited"))
      (libsource (lib "Miscellaneous Devices") (part "Res2"))
    )
    (comp (ref "R4")
      (value "4.7K")
      (footprint "0805R")
      (description "Resistor")
      (fields (field (name "Comment") "RC0805JR-074700RL") (field (name "PUBLISHER") "Altium Limited"))
      (libsource (lib "Miscellaneous Devices") (part "Res2"))
    )
    (comp (ref "R5")
      (value "10D470K")
      (footprint "mov")
      (description "Varistor (Voltage-Sensitive Resistor)")
      (fields (field (name "PUBLISHER") "Altium Limited"))
      (libsource (lib "Miscellaneous Devices") (part "Res Varistor"))
    )
    (comp (ref "R6")
      (value "1K")
      (footprint "0805R")
      (description "Resistor")
      (fields (field (name "Comment") "RC0805JR-071KL") (field (name "PUBLISHER") "Altium Limited"))
      (libsource (lib "Miscellaneous Devices") (part "Res2"))
    )
    (comp (ref "R7")
      (value "1K")
      (footprint "0805R")
      (description "Resistor")
      (fields (field (name "Comment") "RC0805JR-071KL") (field (name "PUBLISHER") "Altium Limited"))
      (libsource (lib "Miscellaneous Devices") (part "Res2"))
    )
    (comp (ref "R8")
      (value "10")
      (footprint "0805R")
      (description "Resistor")
      (fields (field (name "Comment") "PNP-200KJBJ26-10R") (field (name "PUBLISHER") "Altium Limited"))
      (libsource (lib "Miscellaneous Devices") (part "Res2"))
    )
    (comp (ref "R9")
      (value "10")
      (footprint "0805R")
      (description "Resistor")
      (fields (field (name "Comment") "PNP-200KJBJ26-10R") (field (name "PUBLISHER") "Altium Limited"))
      (libsource (lib "Miscellaneous Devices") (part "Res2"))
    )
    (comp (ref "R10")
      (value "10K")
      (footprint "0805R")
      (description "Resistor")
      (fields (field (name "Comment") "RC0805JR-0710KRL") (field (name "PUBLISHER") "Altium Limited"))
      (libsource (lib "Miscellaneous Devices") (part "Res2"))
    )
    (comp (ref "R11")
      (value "1K")
      (footprint "0805R")
      (description "Resistor")
      (fields (field (name "Comment") "RC0805JR-071KL") (field (name "PUBLISHER") "Altium Limited"))
      (libsource (lib "") (part "Res2_2"))
    )
    (comp (ref "R12")
      (value "10K")
      (footprint "0805R")
      (description "Resistor")
      (fields (field (name "Comment") "RC0805JR-0710KRL") (field (name "PUBLISHER") "Altium Limited"))
      (libsource (lib "Miscellaneous Devices") (part "Res2"))
    )
    (comp (ref "R13")
      (value "1K")
      (footprint "0805R")
      (description "Resistor")
      (fields (field (name "Comment") "RC0805JR-071KL") (field (name "PUBLISHER") "Altium Limited"))
      (libsource (lib "") (part "Res2_2"))
    )
    (comp (ref "R14")
      (value "470")
      (footprint "0805R")
      (description "Resistor")
      (fields (field (name "Comment") "RC0805JR-07470RL") (field (name "PUBLISHER") "Altium Limited"))
      (libsource (lib "Miscellaneous Devices") (part "Res2"))
    )
    (comp (ref "R15")
      (value "470")
      (footprint "0805R")
      (description "Resistor")
      (fields (field (name "Comment") "RC0805JR-07470RL") (field (name "PUBLISHER") "Altium Limited"))
      (libsource (lib "Miscellaneous Devices") (part "Res2"))
    )
    (comp (ref "R16")
      (value "470")
      (footprint "0805R")
      (description "Resistor")
      (fields (field (name "Comment") "RC0805JR-07470RL") (field (name "PUBLISHER") "Altium Limited"))
      (libsource (lib "Miscellaneous Devices") (part "Res2"))
    )
    (comp (ref "R17")
      (value "470")
      (footprint "0805R")
      (description "Resistor")
      (fields (field (name "Comment") "RC0805JR-07470RL") (field (name "PUBLISHER") "Altium Limited"))
      (libsource (lib "Miscellaneous Devices") (part "Res2"))
    )
    (comp (ref "R18")
      (value "20")
      (footprint "0805R")
      (description "Resistor")
      (fields (field (name "Comment") "RC0805JR-0720RL") (field (name "PUBLISHER") "Altium Limited"))
      (libsource (lib "") (part "Res2_3"))
    )
    (comp (ref "R19")
      (value "20")
      (footprint "0805R")
      (description "Resistor")
      (fields (field (name "Comment") "RC0805JR-0720RL") (field (name "PUBLISHER") "Altium Limited"))
      (libsource (lib "Miscellaneous Devices") (part "Res2"))
    )
    (comp (ref "R20")
      (value "10K")
      (footprint "0805R")
      (description "Resistor")
      (fields (field (name "Comment") "RC0805JR-0710KL") (field (name "PUBLISHER") "Altium Limited"))
      (libsource (lib "Miscellaneous Devices") (part "Res2"))
    )
    (comp (ref "R21")
      (value "10K")
      (footprint "0805R")
      (description "Resistor")
      (fields (field (name "Comment") "RC0805JR-0710KL") (field (name "PUBLISHER") "Altium Limited"))
      (libsource (lib "Miscellaneous Devices") (part "Res2"))
    )
    (comp (ref "R22")
      (value "120")
      (footprint "0805R")
      (description "Resistor")
      (fields (field (name "Comment") "RC0805JR-07120RL") (field (name "PUBLISHER") "Altium Limited"))
      (libsource (lib "") (part "Res2_1"))
    )
    (comp (ref "R23")
      (value "1K")
      (footprint "0805R")
      (description "Resistor")
      (fields (field (name "Comment") "RC0805JR-071KL") (field (name "PUBLISHER") "Altium Limited"))
      (libsource (lib "Miscellaneous Devices") (part "Res2"))
    )
    (comp (ref "R24")
      (value "1K")
      (footprint "0805R")
      (description "Resistor")
      (fields (field (name "Comment") "RC0805JR-071KL") (field (name "PUBLISHER") "Altium Limited"))
      (libsource (lib "Miscellaneous Devices") (part "Res2"))
    )
    (comp (ref "R25")
      (value "1K")
      (footprint "0805R")
      (description "Resistor")
      (fields (field (name "Comment") "RC0805JR-071KL") (field (name "PUBLISHER") "Altium Limited"))
      (libsource (lib "Miscellaneous Devices") (part "Res2"))
    )
    (comp (ref "R26")
      (value "1K")
      (footprint "0805R")
      (description "Resistor")
      (fields (field (name "Comment") "RC0805JR-071KL") (field (name "PUBLISHER") "Altium Limited"))
      (libsource (lib "Miscellaneous Devices") (part "Res2"))
    )
    (comp (ref "R27")
      (value "1K")
      (footprint "0805R")
      (description "Resistor")
      (fields (field (name "Comment") "RC0805JR-071KL") (field (name "PUBLISHER") "Altium Limited"))
      (libsource (lib "Miscellaneous Devices") (part "Res2"))
    )
    (comp (ref "R28")
      (value "1K")
      (footprint "0805R")
      (description "Resistor")
      (fields (field (name "Comment") "RC0805JR-071KL") (field (name "PUBLISHER") "Altium Limited"))
      (libsource (lib "Miscellaneous Devices") (part "Res2"))
    )
    (comp (ref "R29")
      (value "1K")
      (footprint "0805R")
      (description "Resistor")
      (fields (field (name "Comment") "RC0805JR-071KL") (field (name "PUBLISHER") "Altium Limited"))
      (libsource (lib "Miscellaneous Devices") (part "Res2"))
    )
    (comp (ref "R30")
      (value "1K")
      (footprint "0805R")
      (description "Resistor")
      (fields (field (name "Comment") "RC0805JR-071KL") (field (name "PUBLISHER") "Altium Limited"))
      (libsource (lib "Miscellaneous Devices") (part "Res2"))
    )
    (comp (ref "R31")
      (value "1K")
      (footprint "0805R")
      (description "Resistor")
      (fields (field (name "Comment") "RC0805JR-071KL") (field (name "PUBLISHER") "Altium Limited"))
      (libsource (lib "") (part "Res2_2"))
    )
    (comp (ref "R32")
      (value "1K")
      (footprint "0805R")
      (description "Resistor")
      (fields (field (name "Comment") "RC0805JR-071KL") (field (name "PUBLISHER") "Altium Limited"))
      (libsource (lib "") (part "Res2_2"))
    )
    (comp (ref "R33")
      (value "1K")
      (footprint "0805R")
      (description "Resistor")
      (fields (field (name "Comment") "RC0805JR-071KL") (field (name "PUBLISHER") "Altium Limited"))
      (libsource (lib "") (part "Res2_2"))
    )
    (comp (ref "R34")
      (value "1K")
      (footprint "0805R")
      (description "Resistor")
      (fields (field (name "Comment") "RC0805JR-071KL") (field (name "PUBLISHER") "Altium Limited"))
      (libsource (lib "") (part "Res2_2"))
    )
    (comp (ref "R35")
      (value "3K")
      (footprint "0805R")
      (description "Resistor")
      (fields (field (name "Comment") "RC0805JR-073KL") (field (name "PUBLISHER") "Altium Limited"))
      (libsource (lib "") (part "Res2_3"))
    )
    (comp (ref "R36")
      (value "10K")
      (footprint "0805R")
      (description "Resistor")
      (fields (field (name "Comment") "RC0805JR-0710KL") (field (name "PUBLISHER") "Altium Limited"))
      (libsource (lib "") (part "Res2_2"))
    )
    (comp (ref "R37")
      (value "3K")
      (footprint "0805R")
      (description "Resistor")
      (fields (field (name "Comment") "RC0805JR-073KL") (field (name "PUBLISHER") "Altium Limited"))
      (libsource (lib "") (part "Res2_2"))
    )
    (comp (ref "R38")
      (value "10K")
      (footprint "0805R")
      (description "Resistor")
      (fields (field (name "Comment") "RC0805JR-0710KL") (field (name "PUBLISHER") "Altium Limited"))
      (libsource (lib "") (part "Res2_2"))
    )
    (comp (ref "R39")
      (value "0R")
      (footprint "0805R")
      (description "Resistor")
      (fields (field (name "Comment") "RC0805JR-000KL") (field (name "PUBLISHER") "Altium Limited"))
      (libsource (lib "") (part "Res2_3"))
    )
    (comp (ref "R40")
      (value "15")
      (footprint "0805R")
      (description "Resistor")
      (fields (field (name "Comment") "RC0805JR-0715RL") (field (name "PUBLISHER") "Altium Limited"))
      (libsource (lib "") (part "Res2_3"))
    )
    (comp (ref "R41")
      (value "RC0805JR-0715RL")
      (footprint "0805R")
      (description "Resistor")
      (fields (field (name "ALTIUM_VALUE") "15") (field (name "PUBLISHER") "Altium Limited"))
      (libsource (lib "Miscellaneous Devices") (part "Res2"))
    )
    (comp (ref "R42")
      (value "5.6K")
      (footprint "0805R")
      (description "Resistor")
      (fields (field (name "Comment") "RC0805JR-075600RL") (field (name "PUBLISHER") "Altium Limited"))
      (libsource (lib "") (part "Res2_3"))
    )
    (comp (ref "R43")
      (value "5.6K")
      (footprint "0805R")
      (description "Resistor")
      (fields (field (name "Comment") "RC0805JR-075600RL") (field (name "PUBLISHER") "Altium Limited"))
      (libsource (lib "") (part "Res2_2"))
    )
    (comp (ref "R44")
      (value "8.2K")
      (footprint "0805R")
      (description "Resistor")
      (fields (field (name "Comment") "RC0805JR-078200RL") (field (name "PUBLISHER") "Altium Limited"))
      (libsource (lib "") (part "Res2_2"))
    )
    (comp (ref "R45")
      (value "1K")
      (footprint "0805R")
      (description "Resistor")
      (fields (field (name "Comment") "RC0805JR-071KL") (field (name "PUBLISHER") "Altium Limited"))
      (libsource (lib "Miscellaneous Devices") (part "Res2"))
    )
    (comp (ref "R46")
      (value "1K")
      (footprint "0805R")
      (description "Resistor")
      (fields (field (name "Comment") "RC0805JR-071KL") (field (name "PUBLISHER") "Altium Limited"))
      (libsource (lib "Miscellaneous Devices") (part "Res2"))
    )
    (comp (ref "R47")
      (value "1K")
      (footprint "0805R")
      (description "Resistor")
      (fields (field (name "Comment") "RC0805JR-071KL") (field (name "PUBLISHER") "Altium Limited"))
      (libsource (lib "Miscellaneous Devices") (part "Res2"))
    )
    (comp (ref "R48")
      (value "470")
      (footprint "0805R")
      (description "Resistor")
      (fields (field (name "Comment") "RC0805JR-07470RL") (field (name "PUBLISHER") "Altium Limited"))
      (libsource (lib "Miscellaneous Devices") (part "Res2"))
    )
    (comp (ref "R49")
      (value "470")
      (footprint "0805R")
      (description "Resistor")
      (fields (field (name "Comment") "RC0805JR-07470RL") (field (name "PUBLISHER") "Altium Limited"))
      (libsource (lib "Miscellaneous Devices") (part "Res2"))
    )
    (comp (ref "R50")
      (value "1K")
      (footprint "0805R")
      (description "Resistor")
      (fields (field (name "Comment") "RC0805JR-071KL") (field (name "PUBLISHER") "Altium Limited"))
      (libsource (lib "Miscellaneous Devices") (part "Res2"))
    )
    (comp (ref "R51")
      (value "1K")
      (footprint "0805R")
      (description "Resistor")
      (fields (field (name "Comment") "RC0805JR-071KL") (field (name "PUBLISHER") "Altium Limited"))
      (libsource (lib "Miscellaneous Devices") (part "Res2"))
    )
    (comp (ref "R52")
      (value "1K")
      (footprint "0805R")
      (description "Resistor")
      (fields (field (name "Comment") "RC0805JR-071KL") (field (name "PUBLISHER") "Altium Limited"))
      (libsource (lib "Miscellaneous Devices") (part "Res2"))
    )
    (comp (ref "R53")
      (value "470")
      (footprint "0805R")
      (description "Resistor")
      (fields (field (name "Comment") "RC0805JR-07470RL") (field (name "PUBLISHER") "Altium Limited"))
      (libsource (lib "Miscellaneous Devices") (part "Res2"))
    )
    (comp (ref "R54")
      (value "100R")
      (footprint "0805R")
      (description "Resistor")
      (fields (field (name "Comment") "RC0805JR-07100RL") (field (name "PUBLISHER") "Altium Limited"))
      (libsource (lib "Miscellaneous Devices") (part "Res2"))
    )
    (comp (ref "R55")
      (value "RPot")
      (footprint "VR5")
      (description "Potentiometer")
      (fields (field (name "PUBLISHER") "Altium Limited"))
      (libsource (lib "Standard-V0.0") (part "RPot"))
    )
    (comp (ref "R56")
      (value "100M")
      (footprint "0805R")
      (description "Resistor")
      (fields (field (name "Comment") "RC0805JR-07100ML") (field (name "PUBLISHER") "Altium Limited"))
      (libsource (lib "Miscellaneous Devices") (part "Res2"))
    )
    (comp (ref "R57")
      (value "2K")
      (footprint "0805R")
      (description "Resistor")
      (fields (field (name "Comment") "RC0805JR-072KL") (field (name "PUBLISHER") "Altium Limited"))
      (libsource (lib "Miscellaneous Devices") (part "Res2"))
    )
    (comp (ref "R58")
      (value "5.6K")
      (footprint "0805R")
      (description "Resistor")
      (fields (field (name "Comment") "RC0805JR-075600RL") (field (name "PUBLISHER") "Altium Limited"))
      (libsource (lib "Miscellaneous Devices") (part "Res2"))
    )
    (comp (ref "R59")
      (value "1M")
      (footprint "0805R")
      (description "Resistor")
      (fields (field (name "Comment") "RC0805JR-071000KL") (field (name "PUBLISHER") "Altium Limited"))
      (libsource (lib "") (part "Res2_2"))
    )
    (comp (ref "R60")
      (value "68K")
      (footprint "0805R")
      (description "Resistor")
      (fields (field (name "Comment") "RC0805JR-0768KL") (field (name "PUBLISHER") "Altium Limited"))
      (libsource (lib "") (part "Res2_2"))
    )
    (comp (ref "R61")
      (value "RPot")
      (footprint "VR5")
      (description "Potentiometer")
      (fields (field (name "PUBLISHER") "Altium Limited"))
      (libsource (lib "Standard-V0.0") (part "RPot"))
    )
    (comp (ref "R62")
      (value "68K")
      (footprint "0805R")
      (description "Resistor")
      (fields (field (name "Comment") "RC0805JR-0768KL") (field (name "PUBLISHER") "Altium Limited"))
      (libsource (lib "Miscellaneous Devices") (part "Res2"))
    )
    (comp (ref "R63")
      (value "2K")
      (footprint "0805R")
      (description "Resistor")
      (fields (field (name "Comment") "RC0805JR-072KL") (field (name "PUBLISHER") "Altium Limited"))
      (libsource (lib "Miscellaneous Devices") (part "Res2"))
    )
    (comp (ref "R64")
      (value "1K")
      (footprint "0805R")
      (description "Resistor")
      (fields (field (name "Comment") "RC0805JR-071KL") (field (name "PUBLISHER") "Altium Limited"))
      (libsource (lib "Miscellaneous Devices") (part "Res2"))
    )
    (comp (ref "R65")
      (value "1K")
      (footprint "0805R")
      (description "Resistor")
      (fields (field (name "Comment") "RC0805JR-071KL") (field (name "PUBLISHER") "Altium Limited"))
      (libsource (lib "Miscellaneous Devices") (part "Res2"))
    )
    (comp (ref "R66")
      (value "1K")
      (footprint "0805R")
      (description "Resistor")
      (fields (field (name "Comment") "RC0805JR-071KL") (field (name "PUBLISHER") "Altium Limited"))
      (libsource (lib "Miscellaneous Devices") (part "Res2"))
    )
    (comp (ref "R67")
      (value "10K")
      (footprint "0805R")
      (description "Resistor")
      (fields (field (name "Comment") "RC0805JR-0710KL") (field (name "PUBLISHER") "Altium Limited"))
      (libsource (lib "Miscellaneous Devices") (part "Res2"))
    )
    (comp (ref "R68")
      (value "RC0805JR-07470RL")
      (footprint "0805R")
      (description "Resistor")
      (fields (field (name "ALTIUM_VALUE") "470") (field (name "PUBLISHER") "Altium Limited"))
      (libsource (lib "") (part "Res2_3"))
    )
    (comp (ref "R69")
      (value "2K")
      (footprint "0805R")
      (description "Resistor")
      (fields (field (name "Comment") "RC0805JR-072KL") (field (name "PUBLISHER") "Altium Limited"))
      (libsource (lib "Miscellaneous Devices") (part "Res2"))
    )
    (comp (ref "R70")
      (value "2K")
      (footprint "0805R")
      (description "Resistor")
      (fields (field (name "Comment") "RC0805JR-072KL") (field (name "PUBLISHER") "Altium Limited"))
      (libsource (lib "Miscellaneous Devices") (part "Res2"))
    )
    (comp (ref "R71")
      (value "3.3K")
      (footprint "0805R")
      (description "Resistor")
      (fields (field (name "Comment") "RC0805JR-073300RL") (field (name "PUBLISHER") "Altium Limited"))
      (libsource (lib "Miscellaneous Devices") (part "Res2"))
    )
    (comp (ref "R72")
      (value "4.7K")
      (footprint "0805R")
      (description "Resistor")
      (fields (field (name "Comment") "RC0805JR-074700RL") (field (name "PUBLISHER") "Altium Limited"))
      (libsource (lib "Miscellaneous Devices") (part "Res2"))
    )
    (comp (ref "R73")
      (value "100M")
      (footprint "0805R")
      (description "Resistor")
      (fields (field (name "Comment") "RC0805JR-07100ML") (field (name "PUBLISHER") "Altium Limited"))
      (libsource (lib "") (part "Res2_3"))
    )
    (comp (ref "R74")
      (value "RPot")
      (footprint "VR5")
      (description "Potentiometer")
      (fields (field (name "PUBLISHER") "Altium Limited"))
      (libsource (lib "Standard-V0.0") (part "RPot"))
    )
    (comp (ref "R75")
      (value "10K")
      (footprint "0805R")
      (description "Resistor")
      (fields (field (name "Comment") "RC0805JR-0710KL") (field (name "PUBLISHER") "Altium Limited"))
      (libsource (lib "") (part "Res2_3"))
    )
    (comp (ref "R76")
      (value "3K")
      (footprint "0805R")
      (description "Resistor")
      (fields (field (name "Comment") "RC0805JR-073KL") (field (name "PUBLISHER") "Altium Limited"))
      (libsource (lib "") (part "Res2_1"))
    )
    (comp (ref "R77")
      (value "1K")
      (footprint "0805R")
      (description "Resistor")
      (fields (field (name "Comment") "RC0805JR-071KL") (field (name "PUBLISHER") "Altium Limited"))
      (libsource (lib "Miscellaneous Devices") (part "Res2"))
    )
    (comp (ref "U1")
      (value "WRB_ST(SD)-3WR2")
      (footprint "WRB_ST(SD)-3WR2")
      (libsource (lib "Standard-V0.0") (part "WRB_ST(SD)-3WR2"))
    )
    (comp (ref "U2")
      (value "HCPL063A")
      (footprint "SO-8-N")
      (libsource (lib "Standard-V0.0") (part "HCPL063A"))
    )
    (comp (ref "U3")
      (value "LM1117IMP")
      (footprint "SOT223_M")
      (libsource (lib "Standard-V0.0") (part "LM1117IMP"))
    )
    (comp (ref "U4")
      (value "A05_S-1WR3")
      (footprint "A05_S-1WR3")
      (libsource (lib "Standard-V0.0") (part "A05_S-1WR3"))
    )
    (comp (ref "U5")
      (value "F0505XT-W2R3")
      (footprint "F0505XT-W2R3")
      (libsource (lib "Standard-V0.0") (part "F0505XT-W2R3"))
    )
    (comp (ref "U6")
      (value "STC12C5620AD")
      (footprint "SOP20")
      (libsource (lib "Standard-V0.0") (part "STC12C5620AD"))
    )
    (comp (ref "U7")
      (value "HCPL-061A")
      (footprint "SO-8-N")
      (libsource (lib "Standard-V0.0") (part "6N137"))
    )
    (comp (ref "U8")
      (value "HCPL063A")
      (footprint "SO-8-N")
      (libsource (lib "Standard-V0.0") (part "HCPL063A"))
    )
    (comp (ref "U9")
      (value "HCPL063A")
      (footprint "SO-8-N")
      (libsource (lib "Standard-V0.0") (part "HCPL063A"))
    )
    (comp (ref "U10")
      (value "HCPL063A")
      (footprint "SO-8-N")
      (libsource (lib "Standard-V0.0") (part "HCPL063A"))
    )
    (comp (ref "U11")
      (value "SN65LBC184")
      (footprint "so-8-n")
      (libsource (lib "TI_Sch_Lib") (part "SNx5LBC184"))
    )
    (comp (ref "U12") (value "DAC7611U") (footprint "so-8-n") (libsource (lib "TI_Sch_Lib") (part "DAC7611")))
    (comp (ref "U13") (value "TL431") (footprint "SOT-23-3") (libsource (lib "TI_Sch_Lib") (part "TL431")))
    (comp (ref "U14")
      (value "AD7124-8")
      (footprint "TI-RHB32-3150X3150TP_V")
      (libsource (lib "AD_Sch_Lib") (part "AD7124-8"))
    )
    (comp (ref "U15")
      (value "XTR111")
      (footprint "S-PDSO-G10")
      (libsource (lib "Standard-V0.0") (part "XTR111"))
    )
    (comp (ref "U16")
      (value "TL062ACD")
      (footprint "so-8-n")
      (fields (field (name "MANUFACTURER") "Texas Instruments"))
      (libsource (lib "TI Amplifiers and Linear Operational Amplifier General Purpose") (part "TL062ACD"))
    )
    (comp (ref "Y1")
      (value "XTAL")
      (footprint "11.0592MHz")
      (description "Crystal Oscillator")
      (fields (field (name "PUBLISHER") "Altium Limited"))
      (libsource (lib "Miscellaneous Devices") (part "XTAL"))
    )
  )
  (nets
    (net (code "1") (name "-15V") (class "Default")
      (node (ref "C19") (pin "1") (pinfunction "1_1") (pintype "passive"))
      (node (ref "C20") (pin "2") (pinfunction "2_2") (pintype "passive"))
      (node (ref "C61") (pin "1") (pinfunction "1_1") (pintype "passive"))
      (node (ref "C63") (pin "2") (pinfunction "2_2") (pintype "passive"))
      (node (ref "R55") (pin "3") (pinfunction "TOP_3") (pintype "passive"))
      (node (ref "R74") (pin "3") (pinfunction "TOP_3") (pintype "passive"))
      (node (ref "U16") (pin "4") (pinfunction "VCC-_4") (pintype "power_in"))
      (node (ref "U2") (pin "3") (pinfunction "CATHODE_2_3") (pintype "passive"))
      (node (ref "U4") (pin "4") (pinfunction "-VO_4") (pintype "passive"))
    )
    (net (code "2") (name "/5VON") (class "Default")
      (node (ref "R11") (pin "2") (pinfunction "2_2") (pintype "passive"))
      (node (ref "U2") (pin "7") (pinfunction "VO1_7") (pintype "passive"))
      (node (ref "U6") (pin "8") (pinfunction "ECI/T0/P3.4_8") (pintype "passive"))
    )
    (net (code "3") (name "/485WR{slash}RD") (class "Default")
      (node (ref "R12") (pin "2") (pinfunction "2_2") (pintype "passive"))
      (node (ref "U11") (pin "2") (pinfunction "~{RE}_2") (pintype "passive"))
      (node (ref "U11") (pin "3") (pinfunction "DE_3") (pintype "passive"))
      (node (ref "U8") (pin "6") (pinfunction "VO2_6") (pintype "passive"))
    )
    (net (code "4") (name "/A1") (class "Default")
      (node (ref "R14") (pin "2") (pinfunction "2_2") (pintype "passive"))
      (node (ref "U6") (pin "15") (pinfunction "P1.3/ADC3_15") (pintype "passive"))
    )
    (net (code "5") (name "/A2") (class "Default")
      (node (ref "R15") (pin "2") (pinfunction "2_2") (pintype "passive"))
      (node (ref "U6") (pin "14") (pinfunction "P1.2/ADC2_14") (pintype "passive"))
    )
    (net (code "6") (name "/A3") (class "Default")
      (node (ref "R16") (pin "2") (pinfunction "2_2") (pintype "passive"))
      (node (ref "U6") (pin "13") (pinfunction "P1.1/ADC1/CLKOUT1_13") (pintype "passive"))
    )
    (net (code "7") (name "/A4") (class "Default")
      (node (ref "R17") (pin "2") (pinfunction "2_2") (pintype "passive"))
      (node (ref "U6") (pin "12") (pinfunction "P1.0/ADC0/CLKOUT0_12") (pintype "passive"))
    )
    (net (code "8") (name "/AIN8") (class "Default")
      (node (ref "R54") (pin "1") (pinfunction "1_1") (pintype "passive"))
      (node (ref "U14") (pin "14") (pinfunction "AIN8/IOUT/VBIAS_14") (pintype "passive"))
    )
    (net (code "9") (name "/AIN11") (class "Default")
      (node (ref "C58") (pin "1") (pinfunction "1_1") (pintype "passive"))
      (node (ref "R47") (pin "1") (pinfunction "1_1") (pintype "passive"))
      (node (ref "U14") (pin "17") (pinfunction "AIN11/IOUT/VBIAS_17") (pintype "passive"))
    )
    (net (code "10") (name "/CHN1_N") (class "Default")
      (node (ref "C44") (pin "2") (pinfunction "2_2") (pintype "passive"))
      (node (ref "C45") (pin "1") (pinfunction "1_1") (pintype "passive"))
      (node (ref "R30") (pin "1") (pinfunction "1_1") (pintype "passive"))
      (node (ref "U14") (pin "4") (pinfunction "AIN0/IOUT/VBIAS_4") (pintype "passive"))
    )
    (net (code "11") (name "/CHN1_P") (class "Default")
      (node (ref "C43") (pin "1") (pinfunction "1_1") (pintype "passive"))
      (node (ref "C44") (pin "1") (pinfunction "1_1") (pintype "passive"))
      (node (ref "R29") (pin "1") (pinfunction "1_1") (pintype "passive"))
      (node (ref "U14") (pin "5") (pinfunction "AIN1/IOUT/VBIAS_5") (pintype "passive"))
    )
    (net (code "12") (name "/CHN2_N") (class "Default")
      (node (ref "C41") (pin "2") (pinfunction "2_2") (pintype "passive"))
      (node (ref "C42") (pin "1") (pinfunction "1_1") (pintype "passive"))
      (node (ref "R28") (pin "1") (pinfunction "1_1") (pintype "passive"))
      (node (ref "U14") (pin "6") (pinfunction "AIN2/IOUT/VBIAS/P1_6") (pintype "passive"))
    )
    (net (code "13") (name "/CHN2_P") (class "Default")
      (node (ref "C40") (pin "1") (pinfunction "1_1") (pintype "passive"))
      (node (ref "C41") (pin "1") (pinfunction "1_1") (pintype "passive"))
      (node (ref "R27") (pin "1") (pinfunction "1_1") (pintype "passive"))
      (node (ref "U14") (pin "7") (pinfunction "AIN3/IOUT/VBIAS/P2_7") (pintype "passive"))
    )
    (net (code "14") (name "/CHN3_N") (class "Default")
      (node (ref "C38") (pin "2") (pinfunction "2_2") (pintype "passive"))
      (node (ref "C39") (pin "1") (pinfunction "1_1") (pintype "passive"))
      (node (ref "R26") (pin "1") (pinfunction "1_1") (pintype "passive"))
      (node (ref "U14") (pin "8") (pinfunction "AIN4/IOUT/VBIAS/P3_8") (pintype "passive"))
    )
    (net (code "15") (name "/CHN3_P") (class "Default")
      (node (ref "C37") (pin "1") (pinfunction "1_1") (pintype "passive"))
      (node (ref "C38") (pin "1") (pinfunction "1_1") (pintype "passive"))
      (node (ref "R25") (pin "1") (pinfunction "1_1") (pintype "passive"))
      (node (ref "U14") (pin "9") (pinfunction "AIN5/IOUT/VBIAS/P4_9") (pintype "passive"))
    )
    (net (code "16") (name "/CHN4_N") (class "Default")
      (node (ref "C35") (pin "2") (pinfunction "2_2") (pintype "passive"))
      (node (ref "C36") (pin "1") (pinfunction "1_1") (pintype "passive"))
      (node (ref "R24") (pin "1") (pinfunction "1_1") (pintype "passive"))
      (node (ref "U14") (pin "10") (pinfunction "AIN6/IOUT/VBIAS_10") (pintype "passive"))
    )
    (net (code "17") (name "/CHN4_P") (class "Default")
      (node (ref "C34") (pin "1") (pinfunction "1_1") (pintype "passive"))
      (node (ref "C35") (pin "1") (pinfunction "1_1") (pintype "passive"))
      (node (ref "R23") (pin "1") (pinfunction "1_1") (pintype "passive"))
      (node (ref "U14") (pin "11") (pinfunction "AIN7/IOUT/VBIAS_11") (pintype "passive"))
    )
    (net (code "18") (name "/CHN5_N") (class "Default")
      (node (ref "C56") (pin "2") (pinfunction "2_2") (pintype "passive"))
      (node (ref "C57") (pin "1") (pinfunction "1_1") (pintype "passive"))
      (node (ref "R46") (pin "1") (pinfunction "1_1") (pintype "passive"))
      (node (ref "U14") (pin "16") (pinfunction "AIN10/IOUT/VBIAS_16") (pintype "passive"))
    )
    (net (code "19") (name "/CHN5_P") (class "Default")
      (node (ref "C55") (pin "1") (pinfunction "1_1") (pintype "passive"))
      (node (ref "C56") (pin "1") (pinfunction "1_1") (pintype "passive"))
      (node (ref "R45") (pin "1") (pinfunction "1_1") (pintype "passive"))
      (node (ref "U14") (pin "15") (pinfunction "AIN9/IOUT/VBIAS_15") (pintype "passive"))
    )
    (net (code "20") (name "/CHN6_N") (class "Default")
      (node (ref "C70") (pin "2") (pinfunction "2_2") (pintype "passive"))
      (node (ref "C71") (pin "1") (pinfunction "1_1") (pintype "passive"))
      (node (ref "R59") (pin "2") (pinfunction "2_2") (pintype "passive"))
      (node (ref "R60") (pin "1") (pinfunction "1_1") (pintype "passive"))
      (node (ref "U14") (pin "19") (pinfunction "AIN13/IOUT/VBIAS_19") (pintype "passive"))
    )
    (net (code "21") (name "/CHN6_P") (class "Default")
      (node (ref "C69") (pin "1") (pinfunction "1_1") (pintype "passive"))
      (node (ref "C70") (pin "1") (pinfunction "1_1") (pintype "passive"))
      (node (ref "R64") (pin "1") (pinfunction "1_1") (pintype "passive"))
      (node (ref "U14") (pin "18") (pinfunction "AIN12/IOUT/VBIAS_18") (pintype "passive"))
    )
    (net (code "22") (name "/CHN7_N") (class "Default")
      (node (ref "C73") (pin "2") (pinfunction "2_2") (pintype "passive"))
      (node (ref "C74") (pin "1") (pinfunction "1_1") (pintype "passive"))
      (node (ref "R66") (pin "1") (pinfunction "1_1") (pintype "passive"))
      (node (ref "U14") (pin "21") (pinfunction "AIN15/IOUT/VBIAS/REFIN2-_21") (pintype "passive"))
    )
    (net (code "23") (name "/CHN7_P") (class "Default")
      (node (ref "C72") (pin "1") (pinfunction "1_1") (pintype "passive"))
      (node (ref "C73") (pin "1") (pinfunction "1_1") (pintype "passive"))
      (node (ref "R65") (pin "1") (pinfunction "1_1") (pintype "passive"))
      (node (ref "U14") (pin "20") (pinfunction "AIN14/IOUT/VBIAS/REFIN2+_20") (pintype "passive"))
    )
    (net (code "24") (name "/D1") (class "Default")
      (node (ref "R31") (pin "2") (pinfunction "2_2") (pintype "passive"))
      (node (ref "U12") (pin "2") (pinfunction "~{CS}_2") (pintype "passive"))
      (node (ref "U9") (pin "7") (pinfunction "VO1_7") (pintype "passive"))
    )
    (net (code "25") (name "/D2") (class "Default")
      (node (ref "R33") (pin "2") (pinfunction "2_2") (pintype "passive"))
      (node (ref "U12") (pin "3") (pinfunction "CLK_3") (pintype "passive"))
      (node (ref "U9") (pin "6") (pinfunction "VO2_6") (pintype "passive"))
    )
    (net (code "26") (name "/D3") (class "Default")
      (node (ref "R32") (pin "2") (pinfunction "2_2") (pintype "passive"))
      (node (ref "U10") (pin "7") (pinfunction "VO1_7") (pintype "passive"))
      (node (ref "U12") (pin "4") (pinfunction "SDI_4") (pintype "passive"))
    )
    (net (code "27") (name "/D4") (class "Default")
      (node (ref "R34") (pin "2") (pinfunction "2_2") (pintype "passive"))
      (node (ref "U10") (pin "6") (pinfunction "VO2_6") (pintype "passive"))
      (node (ref "U12") (pin "5") (pinfunction "~{LD}_5") (pintype "passive"))
    )
    (net (code "28") (name "/DIN") (class "Default")
      (node (ref "U14") (pin "29") (pinfunction "DIN_29") (pintype "passive"))
      (node (ref "U6") (pin "17") (pinfunction "P1.5/MOSI/ADC5_17") (pintype "passive"))
    )
    (net (code "29") (name "/DOUT") (class "Default")
      (node (ref "U14") (pin "28") (pinfunction "DOUT/~{RDY}_28") (pintype "passive"))
      (node (ref "U6") (pin "18") (pinfunction "P1.6/MISO/ADC6_18") (pintype "passive"))
    )
    (net (code "30") (name "/IS") (class "Default")
      (node (ref "Q2") (pin "3") (pinfunction "E_3") (pintype "passive"))
      (node (ref "R41") (pin "2") (pinfunction "2_2") (pintype "passive"))
      (node (ref "U15") (pin "2") (pinfunction "IS_2") (pintype "passive"))
    )
    (net (code "31") (name "/Iout") (class "Default")
      (node (ref "D19") (pin "2") (pinfunction "K_2") (pintype "passive"))
      (node (ref "P5") (pin "2") (pinfunction "2_2") (pintype "passive"))
      (node (ref "R40") (pin "1") (pinfunction "1_1") (pintype "passive"))
    )
    (net (code "32") (name "/PSW") (class "Default")
      (node (ref "R48") (pin "1") (pinfunction "1_1") (pintype "passive"))
      (node (ref "U14") (pin "25") (pinfunction "PSW_25") (pintype "passive"))
    )
    (net (code "33") (name "/PowerOK") (class "Default")
      (node (ref "R75") (pin "1") (pinfunction "1_1") (pintype "passive"))
      (node (ref "U6") (pin "11") (pinfunction "P3.7/PCA0/PWM0_11") (pintype "passive"))
    )
    (net (code "34") (name "/REFIN1_N") (class "Default")
      (node (ref "C53") (pin "2") (pinfunction "2_2") (pintype "passive"))
      (node (ref "C54") (pin "1") (pinfunction "1_1") (pintype "passive"))
      (node (ref "R52") (pin "1") (pinfunction "1_1") (pintype "passive"))
      (node (ref "U14") (pin "13") (pinfunction "REFIN1-_13") (pintype "passive"))
    )
    (net (code "35") (name "/REFIN1_P") (class "Default")
      (node (ref "C52") (pin "1") (pinfunction "1_1") (pintype "passive"))
      (node (ref "C53") (pin "1") (pinfunction "1_1") (pintype "passive"))
      (node (ref "R51") (pin "1") (pinfunction "1_1") (pintype "passive"))
      (node (ref "U14") (pin "12") (pinfunction "REFIN1+_12") (pintype "passive"))
    )
    (net (code "36") (name "/REFOUT") (class "Default")
      (node (ref "NTC1") (pin "2") (pinfunction "2_2") (pintype "passive"))
      (node (ref "R59") (pin "1") (pinfunction "1_1") (pintype "passive"))
      (node (ref "R61") (pin "1") (pinfunction "BOT_1") (pintype "passive"))
      (node (ref "R65") (pin "2") (pinfunction "2_2") (pintype "passive"))
      (node (ref "U14") (pin "22") (pinfunction "REFOUT_22") (pintype "passive"))
    )
    (net (code "37") (name "/RS485_N") (class "Default")
      (node (ref "R19") (pin "2") (pinfunction "2_2") (pintype "passive"))
      (node (ref "U11") (pin "7") (pinfunction "B_7") (pintype "passive"))
    )
    (net (code "38") (name "/RS485_P") (class "Default")
      (node (ref "R18") (pin "1") (pinfunction "1_1") (pintype "passive"))
      (node (ref "U11") (pin "6") (pinfunction "A_6") (pintype "passive"))
    )
    (net (code "39") (name "/RxD") (class "Default")
      (node (ref "U11") (pin "1") (pinfunction "R_1") (pintype "passive"))
      (node (ref "U7") (pin "3") (pinfunction "C_3") (pintype "passive"))
    )
    (net (code "40") (name "/SCLK") (class "Default")
      (node (ref "U14") (pin "30") (pinfunction "SCLK_30") (pintype "passive"))
      (node (ref "U6") (pin "19") (pinfunction "P1.7/SCLK/ADC7_19") (pintype "passive"))
    )
    (net (code "41") (name "/TxD") (class "Default")
      (node (ref "R10") (pin "2") (pinfunction "2_2") (pintype "passive"))
      (node (ref "U11") (pin "4") (pinfunction "D_4") (pintype "passive"))
      (node (ref "U8") (pin "7") (pinfunction "VO1_7") (pintype "passive"))
    )
    (net (code "42") (name "/VG") (class "Default")
      (node (ref "Q2") (pin "1") (pinfunction "C_1") (pintype "passive"))
      (node (ref "Q3") (pin "1") (pinfunction "G_1") (pintype "passive"))
      (node (ref "U15") (pin "3") (pinfunction "VG_3") (pintype "passive"))
    )
    (net (code "43") (name "/VOUT") (class "Default")
      (node (ref "R57") (pin "2") (pinfunction "2_2") (pintype "passive"))
      (node (ref "R70") (pin "1") (pinfunction "1_1") (pintype "passive"))
      (node (ref "U12") (pin "8") (pinfunction "VOUT_8") (pintype "passive"))
    )
    (net (code "44") (name "/VREGS") (class "Default")
      (node (ref "R43") (pin "2") (pinfunction "2_2") (pintype "passive"))
      (node (ref "R44") (pin "1") (pinfunction "1_1") (pintype "passive"))
      (node (ref "U15") (pin "4") (pinfunction "REGS_4") (pintype "passive"))
    )
    (net (code "45") (name "/XTAL_N") (class "Default")
      (node (ref "C5") (pin "1") (pinfunction "1_1") (pintype "passive"))
      (node (ref "U6") (pin "5") (pinfunction "XTAL1_5") (pintype "passive"))
      (node (ref "Y1") (pin "1") (pinfunction "OSC1_1") (pintype "passive"))
    )
    (net (code "46") (name "/XTAL_P") (class "Default")
      (node (ref "C2") (pin "1") (pinfunction "1_1") (pintype "passive"))
      (node (ref "U6") (pin "4") (pinfunction "XTAL2_4") (pintype "passive"))
      (node (ref "Y1") (pin "2") (pinfunction "OSC2_2") (pintype "passive"))
    )
    (net (code "47") (name "/~{CS}") (class "Default")
      (node (ref "U14") (pin "32") (pinfunction "~{C}S_32") (pintype "passive"))
      (node (ref "U6") (pin "16") (pinfunction "P1.4/~{SS}/ADC4_16") (pintype "passive"))
    )
    (net (code "48") (name "/±15VON") (class "Default")
      (node (ref "R13") (pin "2") (pinfunction "2_2") (pintype "passive"))
      (node (ref "U2") (pin "6") (pinfunction "VO2_6") (pintype "passive"))
      (node (ref "U6") (pin "9") (pinfunction "PWM1/PCA1/T1/P3.5_9") (pintype "passive"))
    )
    (net (code "49") (name "3.3VCC") (class "Default")
      (node (ref "C1") (pin "1") (pinfunction "1_1") (pintype "passive"))
      (node (ref "C10") (pin "1") (pinfunction "1_1") (pintype "passive"))
      (node (ref "C14") (pin "1") (pinfunction "1_1") (pintype "passive"))
      (node (ref "C15") (pin "1") (pinfunction "1_1") (pintype "passive"))
      (node (ref "C26") (pin "1") (pinfunction "1_1") (pintype "passive"))
      (node (ref "C27") (pin "1") (pinfunction "1_1") (pintype "passive"))
      (node (ref "C3") (pin "1") (pinfunction "1_1") (pintype "passive"))
      (node (ref "C4") (pin "1") (pinfunction "1_1") (pintype "passive"))
      (node (ref "C64") (pin "1") (pinfunction "1_1") (pintype "passive"))
      (node (ref "C66") (pin "1") (pinfunction "1_1") (pintype "passive"))
      (node (ref "C67") (pin "1") (pinfunction "1_1") (pintype "passive"))
      (node (ref "C68") (pin "1") (pinfunction "1_1") (pintype "passive"))
      (node (ref "C9") (pin "1") (pinfunction "1_1") (pintype "passive"))
      (node (ref "R1") (pin "1") (pinfunction "1_1") (pintype "passive"))
      (node (ref "R11") (pin "1") (pinfunction "1_1") (pintype "passive"))
      (node (ref "R13") (pin "1") (pinfunction "1_1") (pintype "passive"))
      (node (ref "R53") (pin "1") (pinfunction "1_1") (pintype "passive"))
      (node (ref "R76") (pin "2") (pinfunction "2_2") (pintype "passive"))
      (node (ref "U14") (pin "2") (pinfunction "IOVDD_2") (pintype "passive"))
      (node (ref "U14") (pin "26") (pinfunction "AVDD_26") (pintype "passive"))
      (node (ref "U2") (pin "8") (pinfunction "VCC_8") (pintype "passive"))
      (node (ref "U3") (pin "2") (pinfunction "VOUT_2") (pintype "passive"))
      (node (ref "U6") (pin "20") (pinfunction "VCC_20") (pintype "passive"))
      (node (ref "U7") (pin "8") (pinfunction "VCC_8") (pintype "passive"))
    )
    (net (code "50") (name "5VDD") (class "Default")
      (node (ref "C16") (pin "1") (pinfunction "1_1") (pintype "passive"))
      (node (ref "C22") (pin "2") (pinfunction "2_2") (pintype "passive"))
      (node (ref "C23") (pin "1") (pinfunction "1_1") (pintype "passive"))
      (node (ref "C25") (pin "1") (pinfunction "1_1") (pintype "passive"))
      (node (ref "C28") (pin "1") (pinfunction "1_1") (pintype "passive"))
      (node (ref "C29") (pin "1") (pinfunction "1_1") (pintype "passive"))
      (node (ref "C30") (pin "1") (pinfunction "1_1") (pintype "passive"))
      (node (ref "C31") (pin "1") (pinfunction "1_1") (pintype "passive"))
      (node (ref "C32") (pin "1") (pinfunction "1_1") (pintype "passive"))
      (node (ref "C33") (pin "1") (pinfunction "1_1") (pintype "passive"))
      (node (ref "D4") (pin "2") (pinfunction "K_2") (pintype "passive"))
      (node (ref "R10") (pin "1") (pinfunction "1_1") (pintype "passive"))
      (node (ref "R12") (pin "1") (pinfunction "1_1") (pintype "passive"))
      (node (ref "R20") (pin "1") (pinfunction "1_1") (pintype "passive"))
      (node (ref "R3") (pin "2") (pinfunction "2_2") (pintype "passive"))
      (node (ref "R31") (pin "1") (pinfunction "1_1") (pintype "passive"))
      (node (ref "R32") (pin "1") (pinfunction "1_1") (pintype "passive"))
      (node (ref "R33") (pin "1") (pinfunction "1_1") (pintype "passive"))
      (node (ref "R34") (pin "1") (pinfunction "1_1") (pintype "passive"))
      (node (ref "R77") (pin "1") (pinfunction "1_1") (pintype "passive"))
      (node (ref "U10") (pin "8") (pinfunction "VCC_8") (pintype "passive"))
      (node (ref "U11") (pin "8") (pinfunction "VCC_8") (pintype "passive"))
      (node (ref "U5") (pin "5") (pinfunction "VO+_5") (pintype "passive"))
      (node (ref "U8") (pin "8") (pinfunction "VCC_8") (pintype "passive"))
      (node (ref "U9") (pin "8") (pinfunction "VCC_8") (pintype "passive"))
    )
    (net (code "51") (name "5VIN") (class "Default")
      (node (ref "C11") (pin "1") (pinfunction "1_1") (pintype "passive"))
      (node (ref "C12") (pin "2") (pinfunction "2_2") (pintype "passive"))
      (node (ref "C6") (pin "1") (pinfunction "1_1") (pintype "passive"))
      (node (ref "C7") (pin "1") (pinfunction "1_1") (pintype "passive"))
      (node (ref "C8") (pin "1") (pinfunction "1_1") (pintype "passive"))
      (node (ref "U1") (pin "5") (pinfunction "VO+_5") (pintype "passive"))
      (node (ref "U3") (pin "3") (pinfunction "VIN_3") (pintype "passive"))
      (node (ref "U4") (pin "1") (pinfunction "VIN+_1") (pintype "passive"))
      (node (ref "U5") (pin "2") (pinfunction "VIN+_2") (pintype "passive"))
    )
    (net (code "52") (name "5VIN-") (class "Default")
      (node (ref "C1") (pin "2") (pinfunction "2_2") (pintype "passive"))
      (node (ref "C10") (pin "2") (pinfunction "2_2") (pintype "passive"))
      (node (ref "C11") (pin "2") (pinfunction "2_2") (pintype "passive"))
      (node (ref "C12") (pin "1") (pinfunction "1_1") (pintype "passive"))
      (node (ref "C14") (pin "2") (pinfunction "2_2") (pintype "passive"))
      (node (ref "C15") (pin "2") (pinfunction "2_2") (pintype "passive"))
      (node (ref "C2") (pin "2") (pinfunction "2_2") (pintype "passive"))
      (node (ref "C26") (pin "2") (pinfunction "2_2") (pintype "passive"))
      (node (ref "C27") (pin "2") (pinfunction "2_2") (pintype "passive"))
      (node (ref "C3") (pin "2") (pinfunction "2_2") (pintype "passive"))
      (node (ref "C34") (pin "2") (pinfunction "2_2") (pintype "passive"))
      (node (ref "C36") (pin "2") (pinfunction "2_2") (pintype "passive"))
      (node (ref "C37") (pin "2") (pinfunction "2_2") (pintype "passive"))
      (node (ref "C39") (pin "2") (pinfunction "2_2") (pintype "passive"))
      (node (ref "C40") (pin "2") (pinfunction "2_2") (pintype "passive"))
      (node (ref "C42") (pin "2") (pinfunction "2_2") (pintype "passive"))
      (node (ref "C43") (pin "2") (pinfunction "2_2") (pintype "passive"))
      (node (ref "C45") (pin "2") (pinfunction "2_2") (pintype "passive"))
      (node (ref "C5") (pin "2") (pinfunction "2_2") (pintype "passive"))
      (node (ref "C51") (pin "2") (pinfunction "2_2") (pintype "passive"))
      (node (ref "C54") (pin "2") (pinfunction "2_2") (pintype "passive"))
      (node (ref "C55") (pin "2") (pinfunction "2_2") (pintype "passive"))
      (node (ref "C57") (pin "2") (pinfunction "2_2") (pintype "passive"))
      (node (ref "C58") (pin "2") (pinfunction "2_2") (pintype "passive"))
      (node (ref "C6") (pin "2") (pinfunction "2_2") (pintype "passive"))
      (node (ref "C62") (pin "1") (pinfunction "1_1") (pintype "passive"))
      (node (ref "C64") (pin "2") (pinfunction "2_2") (pintype "passive"))
      (node (ref "C66") (pin "2") (pinfunction "2_2") (pintype "passive"))
      (node (ref "C67") (pin "2") (pinfunction "2_2") (pintype "passive"))
      (node (ref "C68") (pin "2") (pinfunction "2_2") (pintype "passive"))
      (node (ref "C69") (pin "2") (pinfunction "2_2") (pintype "passive"))
      (node (ref "C7") (pin "2") (pinfunction "2_2") (pintype "passive"))
      (node (ref "C71") (pin "2") (pinfunction "2_2") (pintype "passive"))
      (node (ref "C72") (pin "2") (pinfunction "2_2") (pintype "passive"))
      (node (ref "C74") (pin "2") (pinfunction "2_2") (pintype "passive"))
      (node (ref "C76") (pin "1") (pinfunction "1_1") (pintype "passive"))
      (node (ref "C8") (pin "2") (pinfunction "2_2") (pintype "passive"))
      (node (ref "C9") (pin "2") (pinfunction "2_2") (pintype "passive"))
      (node (ref "D11") (pin "1") (pinfunction "ANODE_1") (pintype "passive"))
      (node (ref "D12") (pin "1") (pinfunction "ANODE_1") (pintype "passive"))
      (node (ref "D14") (pin "1") (pinfunction "ANODE_1") (pintype "passive"))
      (node (ref "D15") (pin "1") (pinfunction "ANODE_1") (pintype "passive"))
      (node (ref "D17") (pin "1") (pinfunction "ANODE_1") (pintype "passive"))
      (node (ref "D20") (pin "1") (pinfunction "ANODE_1") (pintype "passive"))
      (node (ref "D23") (pin "1") (pinfunction "ANODE_1") (pintype "passive"))
      (node (ref "D24") (pin "1") (pinfunction "ANODE_1") (pintype "passive"))
      (node (ref "D25") (pin "1") (pinfunction "ANODE_1") (pintype "passive"))
      (node (ref "D27") (pin "1") (pinfunction "ANODE_1") (pintype "passive"))
      (node (ref "D28") (pin "1") (pinfunction "ANODE_1") (pintype "passive"))
      (node (ref "D29") (pin "1") (pinfunction "ANODE_1") (pintype "passive"))
      (node (ref "D30") (pin "1") (pinfunction "ANODE_1") (pintype "passive"))
      (node (ref "D6") (pin "1") (pinfunction "ANODE_1") (pintype "passive"))
      (node (ref "D8") (pin "1") (pinfunction "ANODE_1") (pintype "passive"))
      (node (ref "D9") (pin "1") (pinfunction "ANODE_1") (pintype "passive"))
      (node (ref "P2") (pin "3") (pinfunction "3_3") (pintype "passive"))
      (node (ref "Q1") (pin "3") (pinfunction "E_3") (pintype "passive"))
      (node (ref "R2") (pin "1") (pinfunction "1_1") (pintype "passive"))
      (node (ref "R49") (pin "1") (pinfunction "1_1") (pintype "passive"))
      (node (ref "R58") (pin "1") (pinfunction "1_1") (pintype "passive"))
      (node (ref "R62") (pin "1") (pinfunction "1_1") (pintype "passive"))
      (node (ref "U1") (pin "7") (pinfunction "GND_7") (pintype "passive"))
      (node (ref "U10") (pin "2") (pinfunction "CATHODE_1_2") (pintype "passive"))
      (node (ref "U10") (pin "3") (pinfunction "CATHODE_2_3") (pintype "passive"))
      (node (ref "U14") (pin "23") (pinfunction "AVSS_23") (pintype "passive"))
      (node (ref "U14") (pin "3") (pinfunction "DGND_3") (pintype "passive"))
      (node (ref "U2") (pin "5") (pinfunction "GND_5") (pintype "passive"))
      (node (ref "U3") (pin "1") (pinfunction "ADJ_1") (pintype "passive"))
      (node (ref "U4") (pin "2") (pinfunction "VIN-_2") (pintype "passive"))
      (node (ref "U5") (pin "1") (pinfunction "VIN-_1") (pintype "passive"))
      (node (ref "U6") (pin "10") (pinfunction "GND_10") (pintype "passive"))
      (node (ref "U7") (pin "5") (pinfunction "GND_5") (pintype "passive"))
      (node (ref "U8") (pin "2") (pinfunction "CATHODE_1_2") (pintype "passive"))
      (node (ref "U8") (pin "3") (pinfunction "CATHODE_2_3") (pintype "passive"))
      (node (ref "U9") (pin "2") (pinfunction "CATHODE_1_2") (pintype "passive"))
      (node (ref "U9") (pin "3") (pinfunction "CATHODE_2_3") (pintype "passive"))
    )
    (net (code "53") (name "15V") (class "Default")
      (node (ref "C17") (pin "1") (pinfunction "1_1") (pintype "passive"))
      (node (ref "C18") (pin "1") (pinfunction "1_1") (pintype "passive"))
      (node (ref "C49") (pin "1") (pinfunction "1_1") (pintype "passive"))
      (node (ref "C50") (pin "1") (pinfunction "1_1") (pintype "passive"))
      (node (ref "C59") (pin "2") (pinfunction "2_2") (pintype "passive"))
      (node (ref "C60") (pin "2") (pinfunction "2_2") (pintype "passive"))
      (node (ref "D22") (pin "2") (pinfunction "K_2") (pintype "passive"))
      (node (ref "R35") (pin "1") (pinfunction "1_1") (pintype "passive"))
      (node (ref "R4") (pin "2") (pinfunction "2_2") (pintype "passive"))
      (node (ref "R55") (pin "1") (pinfunction "BOT_1") (pintype "passive"))
      (node (ref "R68") (pin "1") (pinfunction "1_1") (pintype "passive"))
      (node (ref "R74") (pin "1") (pinfunction "BOT_1") (pintype "passive"))
      (node (ref "U15") (pin "1") (pinfunction "VSP_1") (pintype "passive"))
      (node (ref "U16") (pin "8") (pinfunction "VCC+_8") (pintype "power_in"))
      (node (ref "U4") (pin "6") (pinfunction "+VO_6") (pintype "passive"))
    )
    (net (code "54") (name "Net-(C51-Pad1)") (class "Default")
      (node (ref "C51") (pin "1") (pinfunction "1_1") (pintype "passive"))
      (node (ref "C52") (pin "2") (pinfunction "2_2") (pintype "passive"))
      (node (ref "R50") (pin "1") (pinfunction "1_1") (pintype "passive"))
      (node (ref "R54") (pin "2") (pinfunction "2_2") (pintype "passive"))
    )
    (net (code "55") (name "Net-(D1-A)") (class "Default")
      (node (ref "D1") (pin "1") (pinfunction "A_1") (pintype "passive"))
      (node (ref "R1") (pin "2") (pinfunction "2_2") (pintype "passive"))
    )
    (net (code "56") (name "Net-(D1-K)") (class "Default")
      (node (ref "D1") (pin "2") (pinfunction "K_2") (pintype "passive"))
      (node (ref "Q1") (pin "1") (pinfunction "C_1") (pintype "passive"))
    )
    (net (code "57") (name "Net-(D2-A)") (class "Default")
      (node (ref "D2") (pin "1") (pinfunction "A_1") (pintype "passive"))
      (node (ref "F1") (pin "2") (pinfunction "2_2") (pintype "passive"))
      (node (ref "R5") (pin "2") (pinfunction "2_2") (pintype "passive"))
    )
    (net (code "58") (name "Net-(D2-K)") (class "Default")
      (node (ref "D2") (pin "2") (pinfunction "K_2") (pintype "passive"))
      (node (ref "R8") (pin "2") (pinfunction "2_2") (pintype "passive"))
      (node (ref "R9") (pin "2") (pinfunction "2_2") (pintype "passive"))
    )
    (net (code "59") (name "Net-(D3-K)") (class "Default")
      (node (ref "C13") (pin "1") (pinfunction "1_1") (pintype "passive"))
      (node (ref "D3") (pin "2") (pinfunction "K_2") (pintype "passive"))
      (node (ref "L1") (pin "1") (pinfunction "1_1") (pintype "passive"))
      (node (ref "R8") (pin "1") (pinfunction "1_1") (pintype "passive"))
      (node (ref "R9") (pin "1") (pinfunction "1_1") (pintype "passive"))
    )
    (net (code "60") (name "Net-(D6-CATHODE)") (class "Default")
      (node (ref "D6") (pin "2") (pinfunction "CATHODE_2") (pintype "passive"))
      (node (ref "D7") (pin "2") (pinfunction "CATHODE_2") (pintype "passive"))
      (node (ref "P3") (pin "1") (pinfunction "1_1") (pintype "passive"))
      (node (ref "R23") (pin "2") (pinfunction "2_2") (pintype "passive"))
    )
    (net (code "61") (name "Net-(D7-ANODE)") (class "Default")
      (node (ref "D7") (pin "1") (pinfunction "ANODE_1") (pintype "passive"))
      (node (ref "D8") (pin "2") (pinfunction "CATHODE_2") (pintype "passive"))
      (node (ref "P3") (pin "2") (pinfunction "2_2") (pintype "passive"))
      (node (ref "R24") (pin "2") (pinfunction "2_2") (pintype "passive"))
    )
    (net (code "62") (name "Net-(D10-ANODE)") (class "Default")
      (node (ref "D10") (pin "1") (pinfunction "ANODE_1") (pintype "passive"))
      (node (ref "D11") (pin "2") (pinfunction "CATHODE_2") (pintype "passive"))
      (node (ref "P3") (pin "4") (pinfunction "4_4") (pintype "passive"))
      (node (ref "R26") (pin "2") (pinfunction "2_2") (pintype "passive"))
    )
    (net (code "63") (name "Net-(D10-CATHODE)") (class "Default")
      (node (ref "D10") (pin "2") (pinfunction "CATHODE_2") (pintype "passive"))
      (node (ref "D9") (pin "2") (pinfunction "CATHODE_2") (pintype "passive"))
      (node (ref "P3") (pin "3") (pinfunction "3_3") (pintype "passive"))
      (node (ref "R25") (pin "2") (pinfunction "2_2") (pintype "passive"))
    )
    (net (code "64") (name "Net-(D12-CATHODE)") (class "Default")
      (node (ref "D12") (pin "2") (pinfunction "CATHODE_2") (pintype "passive"))
      (node (ref "D13") (pin "2") (pinfunction "CATHODE_2") (pintype "passive"))
      (node (ref "P3") (pin "5") (pinfunction "5_5") (pintype "passive"))
      (node (ref "R27") (pin "2") (pinfunction "2_2") (pintype "passive"))
    )
    (net (code "65") (name "Net-(D13-ANODE)") (class "Default")
      (node (ref "D13") (pin "1") (pinfunction "ANODE_1") (pintype "passive"))
      (node (ref "D14") (pin "2") (pinfunction "CATHODE_2") (pintype "passive"))
      (node (ref "P3") (pin "6") (pinfunction "6_6") (pintype "passive"))
      (node (ref "R28") (pin "2") (pinfunction "2_2") (pintype "passive"))
    )
    (net (code "66") (name "Net-(D15-CATHODE)") (class "Default")
      (node (ref "D15") (pin "2") (pinfunction "CATHODE_2") (pintype "passive"))
      (node (ref "D16") (pin "2") (pinfunction "CATHODE_2") (pintype "passive"))
      (node (ref "P3") (pin "7") (pinfunction "7_7") (pintype "passive"))
      (node (ref "R29") (pin "2") (pinfunction "2_2") (pintype "passive"))
    )
    (net (code "67") (name "Net-(D16-ANODE)") (class "Default")
      (node (ref "D16") (pin "1") (pinfunction "ANODE_1") (pintype "passive"))
      (node (ref "D17") (pin "2") (pinfunction "CATHODE_2") (pintype "passive"))
      (node (ref "P3") (pin "8") (pinfunction "8_8") (pintype "passive"))
      (node (ref "R30") (pin "2") (pinfunction "2_2") (pintype "passive"))
    )
    (net (code "68") (name "Net-(D18-A)") (class "Default")
      (node (ref "D18") (pin "1") (pinfunction "A_1") (pintype "passive"))
      (node (ref "D5") (pin "2") (pinfunction "K_2") (pintype "passive"))
      (node (ref "P4") (pin "2") (pinfunction "2_2") (pintype "passive"))
      (node (ref "R19") (pin "1") (pinfunction "1_1") (pintype "passive"))
      (node (ref "R21") (pin "2") (pinfunction "2_2") (pintype "passive"))
      (node (ref "R22") (pin "1") (pinfunction "1_1") (pintype "passive"))
    )
    (net (code "69") (name "Net-(D18-K)") (class "Default")
      (node (ref "D18") (pin "2") (pinfunction "K_2") (pintype "passive"))
      (node (ref "D4") (pin "1") (pinfunction "A_1") (pintype "passive"))
      (node (ref "P4") (pin "1") (pinfunction "1_1") (pintype "passive"))
      (node (ref "R18") (pin "2") (pinfunction "2_2") (pintype "passive"))
      (node (ref "R20") (pin "2") (pinfunction "2_2") (pintype "passive"))
      (node (ref "R22") (pin "2") (pinfunction "2_2") (pintype "passive"))
    )
    (net (code "70") (name "Net-(D20-CATHODE)") (class "Default")
      (node (ref "D20") (pin "2") (pinfunction "CATHODE_2") (pintype "passive"))
      (node (ref "D21") (pin "2") (pinfunction "CATHODE_2") (pintype "passive"))
      (node (ref "P6") (pin "7") (pinfunction "7_7") (pintype "passive"))
      (node (ref "R42") (pin "2") (pinfunction "2_2") (pintype "passive"))
      (node (ref "R50") (pin "2") (pinfunction "2_2") (pintype "passive"))
      (node (ref "R51") (pin "2") (pinfunction "2_2") (pintype "passive"))
    )
    (net (code "71") (name "Net-(D21-ANODE)") (class "Default")
      (node (ref "D21") (pin "1") (pinfunction "ANODE_1") (pintype "passive"))
      (node (ref "D24") (pin "2") (pinfunction "CATHODE_2") (pintype "passive"))
      (node (ref "P6") (pin "6") (pinfunction "6_6") (pintype "passive"))
      (node (ref "R42") (pin "1") (pinfunction "1_1") (pintype "passive"))
      (node (ref "R52") (pin "2") (pinfunction "2_2") (pintype "passive"))
    )
    (net (code "72") (name "Net-(D22-A)") (class "Default")
      (node (ref "C48") (pin "1") (pinfunction "1_1") (pintype "passive"))
      (node (ref "D22") (pin "1") (pinfunction "A_1") (pintype "passive"))
      (node (ref "Q3") (pin "3") (pinfunction "S_3") (pintype "passive"))
      (node (ref "R40") (pin "2") (pinfunction "2_2") (pintype "passive"))
    )
    (net (code "73") (name "Net-(D23-CATHODE)") (class "Default")
      (node (ref "D23") (pin "2") (pinfunction "CATHODE_2") (pintype "passive"))
      (node (ref "P6") (pin "8") (pinfunction "8_8") (pintype "passive"))
      (node (ref "R53") (pin "2") (pinfunction "2_2") (pintype "passive"))
    )
    (net (code "74") (name "Net-(D25-CATHODE)") (class "Default")
      (node (ref "D25") (pin "2") (pinfunction "CATHODE_2") (pintype "passive"))
      (node (ref "D26") (pin "2") (pinfunction "CATHODE_2") (pintype "passive"))
      (node (ref "P6") (pin "5") (pinfunction "5_5") (pintype "passive"))
      (node (ref "R45") (pin "2") (pinfunction "2_2") (pintype "passive"))
    )
    (net (code "75") (name "Net-(D26-ANODE)") (class "Default")
      (node (ref "D26") (pin "1") (pinfunction "ANODE_1") (pintype "passive"))
      (node (ref "D27") (pin "2") (pinfunction "CATHODE_2") (pintype "passive"))
      (node (ref "P6") (pin "4") (pinfunction "4_4") (pintype "passive"))
      (node (ref "R46") (pin "2") (pinfunction "2_2") (pintype "passive"))
    )
    (net (code "76") (name "Net-(D28-CATHODE)") (class "Default")
      (node (ref "D28") (pin "2") (pinfunction "CATHODE_2") (pintype "passive"))
      (node (ref "P6") (pin "3") (pinfunction "3_3") (pintype "passive"))
      (node (ref "R47") (pin "2") (pinfunction "2_2") (pintype "passive"))
    )
    (net (code "77") (name "Net-(D29-CATHODE)") (class "Default")
      (node (ref "D29") (pin "2") (pinfunction "CATHODE_2") (pintype "passive"))
      (node (ref "P6") (pin "2") (pinfunction "2_2") (pintype "passive"))
      (node (ref "R48") (pin "2") (pinfunction "2_2") (pintype "passive"))
    )
    (net (code "78") (name "Net-(D30-CATHODE)") (class "Default")
      (node (ref "D30") (pin "2") (pinfunction "CATHODE_2") (pintype "passive"))
      (node (ref "P6") (pin "1") (pinfunction "1_1") (pintype "passive"))
      (node (ref "R49") (pin "2") (pinfunction "2_2") (pintype "passive"))
    )
    (net (code "79") (name "Net-(D31-K)") (class "Default")
      (node (ref "D31") (pin "2") (pinfunction "K_2") (pintype "passive"))
      (node (ref "P7") (pin "1") (pinfunction "1_1") (pintype "passive"))
      (node (ref "Q4") (pin "3") (pinfunction "E_3") (pintype "passive"))
      (node (ref "R63") (pin "1") (pinfunction "1_1") (pintype "passive"))
    )
    (net (code "80") (name "Net-(F1-Pad1)") (class "Default")
      (node (ref "F1") (pin "1") (pinfunction "1_1") (pintype "passive"))
      (node (ref "P1") (pin "4") (pinfunction "4_4") (pintype "passive"))
    )
    (net (code "81") (name "Net-(NTC1-Pad1)") (class "Default")
      (node (ref "NTC1") (pin "1") (pinfunction "1_1") (pintype "passive"))
      (node (ref "R58") (pin "2") (pinfunction "2_2") (pintype "passive"))
      (node (ref "R66") (pin "2") (pinfunction "2_2") (pintype "passive"))
    )
    (net (code "82") (name "Net-(Q1-B)") (class "Default")
      (node (ref "Q1") (pin "2") (pinfunction "B_2") (pintype "passive"))
      (node (ref "R75") (pin "2") (pinfunction "2_2") (pintype "passive"))
    )
    (net (code "83") (name "Net-(Q2-B)") (class "Default")
      (node (ref "Q2") (pin "2") (pinfunction "B_2") (pintype "passive"))
      (node (ref "Q3") (pin "2") (pinfunction "D_2") (pintype "passive"))
      (node (ref "R41") (pin "1") (pinfunction "1_1") (pintype "passive"))
    )
    (net (code "84") (name "Net-(Q4-B)") (class "Default")
      (node (ref "Q4") (pin "2") (pinfunction "B_2") (pintype "passive"))
      (node (ref "R67") (pin "1") (pinfunction "1_1") (pintype "passive"))
    )
    (net (code "85") (name "Net-(Q4-C)") (class "Default")
      (node (ref "Q4") (pin "1") (pinfunction "C_1") (pintype "passive"))
      (node (ref "R68") (pin "2") (pinfunction "2_2") (pintype "passive"))
    )
    (net (code "86") (name "Net-(R55-TAP)") (class "Default")
      (node (ref "R55") (pin "2") (pinfunction "TAP_2") (pintype "passive"))
      (node (ref "R56") (pin "2") (pinfunction "2_2") (pintype "passive"))
    )
    (net (code "87") (name "Net-(R61-TAP)") (class "Default")
      (node (ref "R61") (pin "2") (pinfunction "TAP_2") (pintype "passive"))
      (node (ref "R64") (pin "2") (pinfunction "2_2") (pintype "passive"))
    )
    (net (code "88") (name "Net-(R61-TOP)") (class "Default")
      (node (ref "R60") (pin "2") (pinfunction "2_2") (pintype "passive"))
      (node (ref "R61") (pin "3") (pinfunction "TOP_3") (pintype "passive"))
      (node (ref "R62") (pin "2") (pinfunction "2_2") (pintype "passive"))
    )
    (net (code "89") (name "Net-(R71-Pad1)") (class "Default")
      (node (ref "R71") (pin "1") (pinfunction "1_1") (pintype "passive"))
      (node (ref "R72") (pin "2") (pinfunction "2_2") (pintype "passive"))
      (node (ref "R73") (pin "1") (pinfunction "1_1") (pintype "passive"))
    )
    (net (code "90") (name "Net-(R74-TAP)") (class "Default")
      (node (ref "R73") (pin "2") (pinfunction "2_2") (pintype "passive"))
      (node (ref "R74") (pin "2") (pinfunction "TAP_2") (pintype "passive"))
    )
    (net (code "91") (name "Net-(U2-ANODE_1)") (class "Default")
      (node (ref "R3") (pin "1") (pinfunction "1_1") (pintype "passive"))
      (node (ref "U2") (pin "1") (pinfunction "ANODE_1_1") (pintype "passive"))
    )
    (net (code "92") (name "Net-(U2-ANODE_2)") (class "Default")
      (node (ref "R4") (pin "1") (pinfunction "1_1") (pintype "passive"))
      (node (ref "U2") (pin "4") (pinfunction "ANODE_2_4") (pintype "passive"))
    )
    (net (code "93") (name "Net-(U6-RST)") (class "Default")
      (node (ref "C4") (pin "2") (pinfunction "2_2") (pintype "passive"))
      (node (ref "R2") (pin "2") (pinfunction "2_2") (pintype "passive"))
      (node (ref "U6") (pin "1") (pinfunction "RST_1") (pintype "passive"))
    )
    (net (code "94") (name "Net-(U6-RxD{slash}P3.0)") (class "Default")
      (node (ref "P2") (pin "2") (pinfunction "2_2") (pintype "passive"))
      (node (ref "R76") (pin "1") (pinfunction "1_1") (pintype "passive"))
      (node (ref "U6") (pin "2") (pinfunction "RxD/P3.0_2") (pintype "passive"))
      (node (ref "U7") (pin "6") (pinfunction "VO_6") (pintype "passive"))
    )
    (net (code "95") (name "Net-(U6-TxD{slash}P3.1)") (class "Default")
      (node (ref "P2") (pin "1") (pinfunction "1_1") (pintype "passive"))
      (node (ref "R6") (pin "2") (pinfunction "2_2") (pintype "passive"))
      (node (ref "U6") (pin "3") (pinfunction "TxD/P3.1_3") (pintype "passive"))
    )
    (net (code "96") (name "Net-(U6-~{INT0}{slash}P3.2)") (class "Default")
      (node (ref "R7") (pin "2") (pinfunction "2_2") (pintype "passive"))
      (node (ref "U6") (pin "6") (pinfunction "~{INT0}/P3.2_6") (pintype "passive"))
    )
    (net (code "97") (name "Net-(U7-A)") (class "Default")
      (node (ref "R77") (pin "2") (pinfunction "2_2") (pintype "passive"))
      (node (ref "U7") (pin "2") (pinfunction "A_2") (pintype "passive"))
    )
    (net (code "98") (name "Net-(U8-ANODE_1)") (class "Default")
      (node (ref "R6") (pin "1") (pinfunction "1_1") (pintype "passive"))
      (node (ref "U8") (pin "1") (pinfunction "ANODE_1_1") (pintype "passive"))
    )
    (net (code "99") (name "Net-(U8-ANODE_2)") (class "Default")
      (node (ref "R7") (pin "1") (pinfunction "1_1") (pintype "passive"))
      (node (ref "U8") (pin "4") (pinfunction "ANODE_2_4") (pintype "passive"))
    )
    (net (code "100") (name "Net-(U9-ANODE_1)") (class "Default")
      (node (ref "R14") (pin "1") (pinfunction "1_1") (pintype "passive"))
      (node (ref "U9") (pin "1") (pinfunction "ANODE_1_1") (pintype "passive"))
    )
    (net (code "101") (name "Net-(U9-ANODE_2)") (class "Default")
      (node (ref "R15") (pin "1") (pinfunction "1_1") (pintype "passive"))
      (node (ref "U9") (pin "4") (pinfunction "ANODE_2_4") (pintype "passive"))
    )
    (net (code "102") (name "Net-(U10-ANODE_1)") (class "Default")
      (node (ref "R16") (pin "1") (pinfunction "1_1") (pintype "passive"))
      (node (ref "U10") (pin "1") (pinfunction "ANODE_1_1") (pintype "passive"))
    )
    (net (code "103") (name "Net-(U10-ANODE_2)") (class "Default")
      (node (ref "R17") (pin "1") (pinfunction "1_1") (pintype "passive"))
      (node (ref "U10") (pin "4") (pinfunction "ANODE_2_4") (pintype "passive"))
    )
    (net (code "104") (name "Net-(U13-REF)") (class "Default")
      (node (ref "R36") (pin "1") (pinfunction "1_1") (pintype "passive"))
      (node (ref "R37") (pin "2") (pinfunction "2_2") (pintype "passive"))
      (node (ref "R38") (pin "1") (pinfunction "1_1") (pintype "passive"))
      (node (ref "U13") (pin "2") (pinfunction "REF_2") (pintype "passive"))
    )
    (net (code "105") (name "Net-(U14-REGCAPA)") (class "Default")
      (node (ref "C76") (pin "2") (pinfunction "2_2") (pintype "passive"))
      (node (ref "U14") (pin "24") (pinfunction "REGCAPA_24") (pintype "passive"))
    )
    (net (code "106") (name "Net-(U14-REGCAPD)") (class "Default")
      (node (ref "C62") (pin "2") (pinfunction "2_2") (pintype "passive"))
      (node (ref "U14") (pin "1") (pinfunction "REGCAPD_1") (pintype "passive"))
    )
    (net (code "107") (name "Net-(U15-SET)") (class "Default")
      (node (ref "R69") (pin "2") (pinfunction "2_2") (pintype "passive"))
      (node (ref "U15") (pin "7") (pinfunction "SET_7") (pintype "passive"))
    )
    (net (code "108") (name "Net-(U15-VIN)") (class "Default")
      (node (ref "C75") (pin "2") (pinfunction "2_2") (pintype "passive"))
      (node (ref "R70") (pin "2") (pinfunction "2_2") (pintype "passive"))
      (node (ref "R71") (pin "2") (pinfunction "2_2") (pintype "passive"))
      (node (ref "U15") (pin "6") (pinfunction "VIN_6") (pintype "passive"))
    )
    (net (code "109") (name "Net-(U16A-IN1+)") (class "Default")
      (node (ref "C65") (pin "1") (pinfunction "1_1") (pintype "passive"))
      (node (ref "R57") (pin "1") (pinfunction "1_1") (pintype "passive"))
      (node (ref "U16") (pin "3") (pinfunction "IN1+_3") (pintype "input"))
    )
    (net (code "110") (name "Net-(U16A-IN1-)") (class "Default")
      (node (ref "R56") (pin "1") (pinfunction "1_1") (pintype "passive"))
      (node (ref "R63") (pin "2") (pinfunction "2_2") (pintype "passive"))
      (node (ref "U16") (pin "2") (pinfunction "IN1-_2") (pintype "input"))
    )
    (net (code "111") (name "Net-(U16A-OUT1)") (class "Default")
      (node (ref "R67") (pin "2") (pinfunction "2_2") (pintype "passive"))
      (node (ref "U16") (pin "1") (pinfunction "OUT1_1") (pintype "output"))
    )
    (net (code "112") (name "SGND") (class "Default")
      (node (ref "C16") (pin "2") (pinfunction "2_2") (pintype "passive"))
      (node (ref "C22") (pin "1") (pinfunction "1_1") (pintype "passive"))
      (node (ref "C23") (pin "2") (pinfunction "2_2") (pintype "passive"))
      (node (ref "C25") (pin "2") (pinfunction "2_2") (pintype "passive"))
      (node (ref "C28") (pin "2") (pinfunction "2_2") (pintype "passive"))
      (node (ref "C29") (pin "2") (pinfunction "2_2") (pintype "passive"))
      (node (ref "C30") (pin "2") (pinfunction "2_2") (pintype "passive"))
      (node (ref "C31") (pin "2") (pinfunction "2_2") (pintype "passive"))
      (node (ref "C32") (pin "2") (pinfunction "2_2") (pintype "passive"))
      (node (ref "C33") (pin "2") (pinfunction "2_2") (pintype "passive"))
      (node (ref "D5") (pin "1") (pinfunction "A_1") (pintype "passive"))
      (node (ref "R21") (pin "1") (pinfunction "1_1") (pintype "passive"))
      (node (ref "R39") (pin "1") (pinfunction "1_1") (pintype "passive"))
      (node (ref "U10") (pin "5") (pinfunction "GND_5") (pintype "passive"))
      (node (ref "U11") (pin "5") (pinfunction "GND_5") (pintype "passive"))
      (node (ref "U2") (pin "2") (pinfunction "CATHODE_1_2") (pintype "passive"))
      (node (ref "U5") (pin "4") (pinfunction "GND_4") (pintype "passive"))
      (node (ref "U8") (pin "5") (pinfunction "GND_5") (pintype "passive"))
      (node (ref "U9") (pin "5") (pinfunction "GND_5") (pintype "passive"))
    )
    (net (code "113") (name "VBIAS") (class "Default")
      (node (ref "R35") (pin "2") (pinfunction "2_2") (pintype "passive"))
      (node (ref "R37") (pin "1") (pinfunction "1_1") (pintype "passive"))
      (node (ref "R72") (pin "1") (pinfunction "1_1") (pintype "passive"))
      (node (ref "U13") (pin "1") (pinfunction "CATHODE_1") (pintype "passive"))
    )
    (net (code "114") (name "VIN+") (class "Default")
      (node (ref "C21") (pin "1") (pinfunction "1_1") (pintype "passive"))
      (node (ref "C24") (pin "1") (pinfunction "1_1") (pintype "passive"))
      (node (ref "L1") (pin "2") (pinfunction "2_2") (pintype "passive"))
      (node (ref "U1") (pin "4") (pinfunction "VIN+_4") (pintype "passive"))
    )
    (net (code "115") (name "VIN-") (class "Default")
      (node (ref "C13") (pin "2") (pinfunction "2_2") (pintype "passive"))
      (node (ref "C21") (pin "2") (pinfunction "2_2") (pintype "passive"))
      (node (ref "C24") (pin "2") (pinfunction "2_2") (pintype "passive"))
      (node (ref "D3") (pin "1") (pinfunction "A_1") (pintype "passive"))
      (node (ref "P1") (pin "1") (pinfunction "1_1") (pintype "passive"))
      (node (ref "R5") (pin "1") (pinfunction "1_1") (pintype "passive"))
      (node (ref "U1") (pin "1") (pinfunction "VIN-_1") (pintype "passive"))
    )
    (net (code "116") (name "VREGF") (class "Default")
      (node (ref "C46") (pin "1") (pinfunction "1_1") (pintype "passive"))
      (node (ref "C47") (pin "2") (pinfunction "2_2") (pintype "passive"))
      (node (ref "R43") (pin "1") (pinfunction "1_1") (pintype "passive"))
      (node (ref "U12") (pin "1") (pinfunction "VDD_1") (pintype "passive"))
      (node (ref "U12") (pin "6") (pinfunction "~{CLR}_6") (pintype "passive"))
      (node (ref "U15") (pin "5") (pinfunction "REGF_5") (pintype "passive"))
    )
    (net (code "117") (name "unconnected-(P1-Pad2)") (class "Default")
      (node (ref "P1") (pin "2") (pinfunction "2_2") (pintype "passive"))
    )
    (net (code "118") (name "unconnected-(P1-Pad3)") (class "Default")
      (node (ref "P1") (pin "3") (pinfunction "3_3") (pintype "passive"))
    )
    (net (code "119") (name "unconnected-(U1-NC-Pad6)") (class "Default")
      (node (ref "U1") (pin "6") (pinfunction "NC_6") (pintype "passive"))
    )
    (net (code "120") (name "unconnected-(U4-NC-Pad3)") (class "Default")
      (node (ref "U4") (pin "3") (pinfunction "NC_3") (pintype "passive"))
    )
    (net (code "121") (name "unconnected-(U5-NC-Pad8)") (class "Default")
      (node (ref "U5") (pin "8") (pinfunction "NC_8") (pintype "passive"))
    )
    (net (code "122") (name "unconnected-(U6-~{INT1}{slash}P3.3-Pad7)") (class "Default")
      (node (ref "U6") (pin "7") (pinfunction "~{INT1}/P3.3_7") (pintype "passive"))
    )
    (net (code "123") (name "unconnected-(U7-NC-Pad1)") (class "Default")
      (node (ref "U7") (pin "1") (pinfunction "NC_1") (pintype "passive"))
    )
    (net (code "124") (name "unconnected-(U7-NC-Pad4)") (class "Default")
      (node (ref "U7") (pin "4") (pinfunction "NC_4") (pintype "passive"))
    )
    (net (code "125") (name "unconnected-(U7-VE-Pad7)") (class "Default")
      (node (ref "U7") (pin "7") (pinfunction "VE_7") (pintype "passive"))
    )
    (net (code "126") (name "unconnected-(U14-CLK-Pad31)") (class "Default")
      (node (ref "U14") (pin "31") (pinfunction "CLK_31") (pintype "passive"))
    )
    (net (code "127") (name "unconnected-(U14-~{SYNC}-Pad27)") (class "Default")
      (node (ref "U14") (pin "27") (pinfunction "~{SYNC}_27") (pintype "passive"))
    )
    (net (code "128") (name "unconnected-(U15-~{EF}-Pad8)") (class "Default")
      (node (ref "U15") (pin "8") (pinfunction "~{EF}_8") (pintype "passive"))
    )
    (net (code "129") (name "±15VGND") (class "Default")
      (node (ref "C17") (pin "2") (pinfunction "2_2") (pintype "passive"))
      (node (ref "C18") (pin "2") (pinfunction "2_2") (pintype "passive"))
      (node (ref "C19") (pin "2") (pinfunction "2_2") (pintype "passive"))
      (node (ref "C20") (pin "1") (pinfunction "1_1") (pintype "passive"))
      (node (ref "C46") (pin "2") (pinfunction "2_2") (pintype "passive"))
      (node (ref "C47") (pin "1") (pinfunction "1_1") (pintype "passive"))
      (node (ref "C48") (pin "2") (pinfunction "2_2") (pintype "passive"))
      (node (ref "C49") (pin "2") (pinfunction "2_2") (pintype "passive"))
      (node (ref "C50") (pin "2") (pinfunction "2_2") (pintype "passive"))
      (node (ref "C59") (pin "1") (pinfunction "1_1") (pintype "passive"))
      (node (ref "C60") (pin "1") (pinfunction "1_1") (pintype "passive"))
      (node (ref "C61") (pin "2") (pinfunction "2_2") (pintype "passive"))
      (node (ref "C63") (pin "1") (pinfunction "1_1") (pintype "passive"))
      (node (ref "C65") (pin "2") (pinfunction "2_2") (pintype "passive"))
      (node (ref "C75") (pin "1") (pinfunction "1_1") (pintype "passive"))
      (node (ref "D19") (pin "1") (pinfunction "A_1") (pintype "passive"))
      (node (ref "D31") (pin "1") (pinfunction "A_1") (pintype "passive"))
      (node (ref "P5") (pin "1") (pinfunction "1_1") (pintype "passive"))
      (node (ref "P7") (pin "2") (pinfunction "2_2") (pintype "passive"))
      (node (ref "R36") (pin "2") (pinfunction "2_2") (pintype "passive"))
      (node (ref "R38") (pin "2") (pinfunction "2_2") (pintype "passive"))
      (node (ref "R39") (pin "2") (pinfunction "2_2") (pintype "passive"))
      (node (ref "R44") (pin "2") (pinfunction "2_2") (pintype "passive"))
      (node (ref "R69") (pin "1") (pinfunction "1_1") (pintype "passive"))
      (node (ref "U12") (pin "7") (pinfunction "GND_7") (pintype "passive"))
      (node (ref "U13") (pin "3") (pinfunction "ANODE_3") (pintype "passive"))
      (node (ref "U15") (pin "10") (pinfunction "GND_10") (pintype "passive"))
      (node (ref "U15") (pin "9") (pinfunction "OD_9") (pintype "passive"))
      (node (ref "U4") (pin "5") (pinfunction "GND_5") (pintype "passive"))
    )
  )
)
